# thermocouple_2.net
KiCad netlist of a schematic drawn in Altium Designer
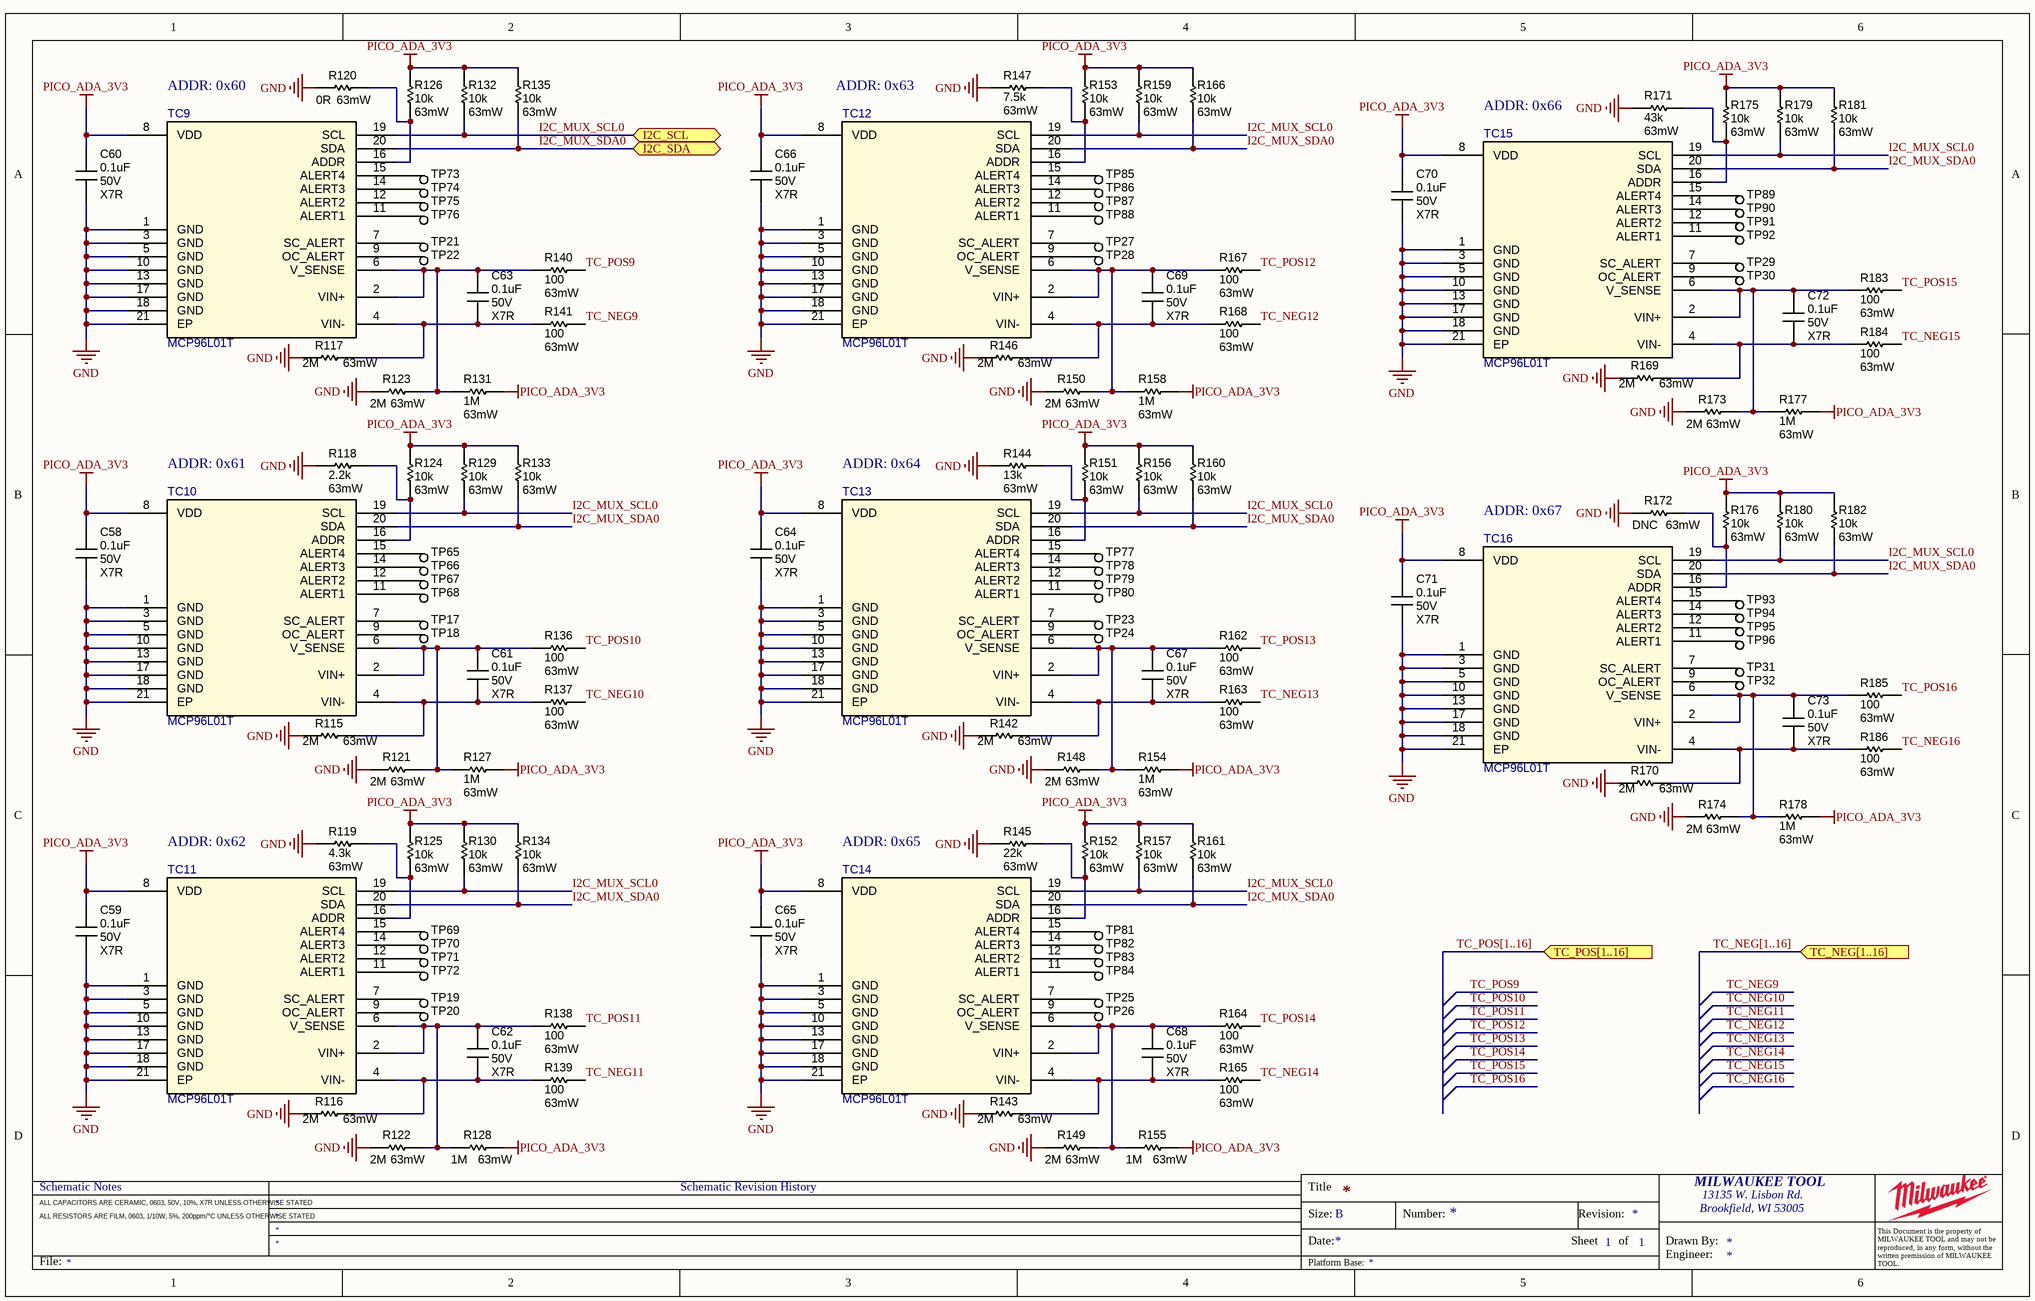
[diagram p0: thermocouple_2.SchDoc]

(export (version "E")
  (design (tool "Eeschema 10.0.6"))
  (components
    (comp (ref "C58")
      (value "0.1uF")
      (footprint "CAPC1608X09N")
      (description "CAP CER 0.1UF 50V X7R 0603")
      (fields
        (field (name "TOLERANCE") "10%")
        (field (name "MFR") "KEMET")
        (field (name "VOLTAGE RATING") "50V")
        (field (name "TEMP COEFF") "X7R")
      )
      (libsource (lib "General_Library") (part "CMP-004-0070"))
    )
    (comp (ref "C59")
      (value "0.1uF")
      (footprint "CAPC1608X09N")
      (description "CAP CER 0.1UF 50V X7R 0603")
      (fields
        (field (name "TOLERANCE") "10%")
        (field (name "MFR") "KEMET")
        (field (name "VOLTAGE RATING") "50V")
        (field (name "TEMP COEFF") "X7R")
      )
      (libsource (lib "General_Library") (part "CMP-004-0070"))
    )
    (comp (ref "C60")
      (value "0.1uF")
      (footprint "CAPC1608X09N")
      (description "CAP CER 0.1UF 50V X7R 0603")
      (fields
        (field (name "TOLERANCE") "10%")
        (field (name "MFR") "KEMET")
        (field (name "VOLTAGE RATING") "50V")
        (field (name "TEMP COEFF") "X7R")
      )
      (libsource (lib "General_Library") (part "CMP-004-0070"))
    )
    (comp (ref "C61")
      (value "0.1uF")
      (footprint "CAPC1005X06N")
      (description "CAP CER SMD 0.1UF 50V X7R 0402")
      (fields
        (field (name "TOLERANCE") "10%")
        (field (name "MFR") "Murata Electronics")
        (field (name "VOLTAGE RATING") "50V")
        (field (name "TEMP COEFF") "X7R")
      )
      (libsource (lib "General_Library") (part "CMP-004-0076"))
    )
    (comp (ref "C62")
      (value "0.1uF")
      (footprint "CAPC1005X06N")
      (description "CAP CER SMD 0.1UF 50V X7R 0402")
      (fields
        (field (name "TOLERANCE") "10%")
        (field (name "MFR") "Murata Electronics")
        (field (name "VOLTAGE RATING") "50V")
        (field (name "TEMP COEFF") "X7R")
      )
      (libsource (lib "General_Library") (part "CMP-004-0076"))
    )
    (comp (ref "C63")
      (value "0.1uF")
      (footprint "CAPC1005X06N")
      (description "CAP CER SMD 0.1UF 50V X7R 0402")
      (fields
        (field (name "TOLERANCE") "10%")
        (field (name "MFR") "Murata Electronics")
        (field (name "VOLTAGE RATING") "50V")
        (field (name "TEMP COEFF") "X7R")
      )
      (libsource (lib "General_Library") (part "CMP-004-0076"))
    )
    (comp (ref "C64")
      (value "0.1uF")
      (footprint "CAPC1608X09N")
      (description "CAP CER 0.1UF 50V X7R 0603")
      (fields
        (field (name "TOLERANCE") "10%")
        (field (name "MFR") "KEMET")
        (field (name "VOLTAGE RATING") "50V")
        (field (name "TEMP COEFF") "X7R")
      )
      (libsource (lib "General_Library") (part "CMP-004-0070"))
    )
    (comp (ref "C65")
      (value "0.1uF")
      (footprint "CAPC1608X09N")
      (description "CAP CER 0.1UF 50V X7R 0603")
      (fields
        (field (name "TOLERANCE") "10%")
        (field (name "MFR") "KEMET")
        (field (name "VOLTAGE RATING") "50V")
        (field (name "TEMP COEFF") "X7R")
      )
      (libsource (lib "General_Library") (part "CMP-004-0070"))
    )
    (comp (ref "C66")
      (value "0.1uF")
      (footprint "CAPC1608X09N")
      (description "CAP CER 0.1UF 50V X7R 0603")
      (fields
        (field (name "TOLERANCE") "10%")
        (field (name "MFR") "KEMET")
        (field (name "VOLTAGE RATING") "50V")
        (field (name "TEMP COEFF") "X7R")
      )
      (libsource (lib "General_Library") (part "CMP-004-0070"))
    )
    (comp (ref "C67")
      (value "0.1uF")
      (footprint "CAPC1005X06N")
      (description "CAP CER SMD 0.1UF 50V X7R 0402")
      (fields
        (field (name "TOLERANCE") "10%")
        (field (name "MFR") "Murata Electronics")
        (field (name "VOLTAGE RATING") "50V")
        (field (name "TEMP COEFF") "X7R")
      )
      (libsource (lib "General_Library") (part "CMP-004-0076"))
    )
    (comp (ref "C68")
      (value "0.1uF")
      (footprint "CAPC1005X06N")
      (description "CAP CER SMD 0.1UF 50V X7R 0402")
      (fields
        (field (name "TOLERANCE") "10%")
        (field (name "MFR") "Murata Electronics")
        (field (name "VOLTAGE RATING") "50V")
        (field (name "TEMP COEFF") "X7R")
      )
      (libsource (lib "General_Library") (part "CMP-004-0076"))
    )
    (comp (ref "C69")
      (value "0.1uF")
      (footprint "CAPC1005X06N")
      (description "CAP CER SMD 0.1UF 50V X7R 0402")
      (fields
        (field (name "TOLERANCE") "10%")
        (field (name "MFR") "Murata Electronics")
        (field (name "VOLTAGE RATING") "50V")
        (field (name "TEMP COEFF") "X7R")
      )
      (libsource (lib "General_Library") (part "CMP-004-0076"))
    )
    (comp (ref "C70")
      (value "0.1uF")
      (footprint "CAPC1608X09N")
      (description "CAP CER 0.1UF 50V X7R 0603")
      (fields
        (field (name "TOLERANCE") "10%")
        (field (name "MFR") "KEMET")
        (field (name "VOLTAGE RATING") "50V")
        (field (name "TEMP COEFF") "X7R")
      )
      (libsource (lib "General_Library") (part "CMP-004-0070"))
    )
    (comp (ref "C71")
      (value "0.1uF")
      (footprint "CAPC1608X09N")
      (description "CAP CER 0.1UF 50V X7R 0603")
      (fields
        (field (name "TOLERANCE") "10%")
        (field (name "MFR") "KEMET")
        (field (name "VOLTAGE RATING") "50V")
        (field (name "TEMP COEFF") "X7R")
      )
      (libsource (lib "General_Library") (part "CMP-004-0070"))
    )
    (comp (ref "C72")
      (value "0.1uF")
      (footprint "CAPC1005X06N")
      (description "CAP CER SMD 0.1UF 50V X7R 0402")
      (fields
        (field (name "TOLERANCE") "10%")
        (field (name "MFR") "Murata Electronics")
        (field (name "VOLTAGE RATING") "50V")
        (field (name "TEMP COEFF") "X7R")
      )
      (libsource (lib "General_Library") (part "CMP-004-0076"))
    )
    (comp (ref "C73")
      (value "0.1uF")
      (footprint "CAPC1005X06N")
      (description "CAP CER SMD 0.1UF 50V X7R 0402")
      (fields
        (field (name "TOLERANCE") "10%")
        (field (name "MFR") "Murata Electronics")
        (field (name "VOLTAGE RATING") "50V")
        (field (name "TEMP COEFF") "X7R")
      )
      (libsource (lib "General_Library") (part "CMP-004-0076"))
    )
    (comp (ref "R115")
      (value "2M")
      (footprint "RESC1005X04N")
      (description "RES SMD 2M OHM 1% 1/16W 0402")
      (fields (field (name "TOLERANCE") "1%") (field (name "MFR") "YAGEO") (field (name "WATTAGE") "63mW"))
      (libsource (lib "General_Library") (part "CMP-025-0172"))
    )
    (comp (ref "R116")
      (value "2M")
      (footprint "RESC1005X04N")
      (description "RES SMD 2M OHM 1% 1/16W 0402")
      (fields (field (name "TOLERANCE") "1%") (field (name "MFR") "YAGEO") (field (name "WATTAGE") "63mW"))
      (libsource (lib "General_Library") (part "CMP-025-0172"))
    )
    (comp (ref "R117")
      (value "2M")
      (footprint "RESC1005X04N")
      (description "RES SMD 2M OHM 1% 1/16W 0402")
      (fields (field (name "TOLERANCE") "1%") (field (name "MFR") "YAGEO") (field (name "WATTAGE") "63mW"))
      (libsource (lib "General_Library") (part "CMP-025-0172"))
    )
    (comp (ref "R118")
      (value "2.2k")
      (footprint "RESC1005X04N")
      (description "RES SMD 2.2K OHM 1% 1/16W 0402")
      (fields (field (name "TOLERANCE") "1%") (field (name "MFR") "YAGEO") (field (name "WATTAGE") "63mW"))
      (libsource (lib "General_Library") (part "CMP-025-0171"))
    )
    (comp (ref "R119")
      (value "4.3k")
      (footprint "RESC1005X04N")
      (description "RES SMD 4.3K OHM 1% 1/16W 0402")
      (fields (field (name "TOLERANCE") "1%") (field (name "MFR") "Yageo") (field (name "WATTAGE") "63mW"))
      (libsource (lib "General_Library") (part "CMP-025-0176"))
    )
    (comp (ref "R120")
      (value "0R")
      (footprint "RESC1005X04N")
      (description "RES SMD 0 OHM JUMPER 1/16W 0402")
      (fields
        (field (name "MFR") "Stackpole Electronics Inc")
        (field (name "TOLERANCE") "Jumper")
        (field (name "WATTAGE") "63mW")
      )
      (libsource (lib "General_Library") (part "CMP-025-0102"))
    )
    (comp (ref "R121")
      (value "2M")
      (footprint "RESC1005X04N")
      (description "RES SMD 2M OHM 1% 1/16W 0402")
      (fields (field (name "TOLERANCE") "1%") (field (name "MFR") "YAGEO") (field (name "WATTAGE") "63mW"))
      (libsource (lib "General_Library") (part "CMP-025-0172"))
    )
    (comp (ref "R122")
      (value "2M")
      (footprint "RESC1005X04N")
      (description "RES SMD 2M OHM 1% 1/16W 0402")
      (fields (field (name "TOLERANCE") "1%") (field (name "MFR") "YAGEO") (field (name "WATTAGE") "63mW"))
      (libsource (lib "General_Library") (part "CMP-025-0172"))
    )
    (comp (ref "R123")
      (value "2M")
      (footprint "RESC1005X04N")
      (description "RES SMD 2M OHM 1% 1/16W 0402")
      (fields (field (name "TOLERANCE") "1%") (field (name "MFR") "YAGEO") (field (name "WATTAGE") "63mW"))
      (libsource (lib "General_Library") (part "CMP-025-0172"))
    )
    (comp (ref "R124")
      (value "10k")
      (footprint "RESC1005X04N")
      (description "RES SMD 10K OHM 0.5% 1/16W 0402")
      (fields
        (field (name "MFR") "Panasonic Electronic Components")
        (field (name "TOLERANCE") "0.5%")
        (field (name "WATTAGE") "63mW")
      )
      (libsource (lib "Schlib1") (part "CMP-025-0026"))
    )
    (comp (ref "R125")
      (value "10k")
      (footprint "RESC1005X04N")
      (description "RES SMD 10K OHM 0.5% 1/16W 0402")
      (fields
        (field (name "MFR") "Panasonic Electronic Components")
        (field (name "TOLERANCE") "0.5%")
        (field (name "WATTAGE") "63mW")
      )
      (libsource (lib "Schlib1") (part "CMP-025-0026"))
    )
    (comp (ref "R126")
      (value "10k")
      (footprint "RESC1005X04N")
      (description "RES SMD 10K OHM 0.5% 1/16W 0402")
      (fields
        (field (name "MFR") "Panasonic Electronic Components")
        (field (name "TOLERANCE") "0.5%")
        (field (name "WATTAGE") "63mW")
      )
      (libsource (lib "Schlib1") (part "CMP-025-0026"))
    )
    (comp (ref "R127")
      (value "1M")
      (footprint "RESC1005X04N")
      (description "RES SMD 1M OHM 1% 1/16W 0402")
      (fields (field (name "TOLERANCE") "1%") (field (name "MFR") "YAGEO") (field (name "WATTAGE") "63mW"))
      (libsource (lib "General_Library") (part "CMP-025-0173"))
    )
    (comp (ref "R128")
      (value "1M")
      (footprint "RESC1005X04N")
      (description "RES SMD 1M OHM 1% 1/16W 0402")
      (fields (field (name "TOLERANCE") "1%") (field (name "MFR") "YAGEO") (field (name "WATTAGE") "63mW"))
      (libsource (lib "General_Library") (part "CMP-025-0173"))
    )
    (comp (ref "R129")
      (value "10k")
      (footprint "RESC1005X04N")
      (description "RES SMD 10K OHM 0.5% 1/16W 0402")
      (fields
        (field (name "MFR") "Panasonic Electronic Components")
        (field (name "TOLERANCE") "0.5%")
        (field (name "WATTAGE") "63mW")
      )
      (libsource (lib "Schlib1") (part "CMP-025-0026"))
    )
    (comp (ref "R130")
      (value "10k")
      (footprint "RESC1005X04N")
      (description "RES SMD 10K OHM 0.5% 1/16W 0402")
      (fields
        (field (name "MFR") "Panasonic Electronic Components")
        (field (name "TOLERANCE") "0.5%")
        (field (name "WATTAGE") "63mW")
      )
      (libsource (lib "Schlib1") (part "CMP-025-0026"))
    )
    (comp (ref "R131")
      (value "1M")
      (footprint "RESC1005X04N")
      (description "RES SMD 1M OHM 1% 1/16W 0402")
      (fields (field (name "TOLERANCE") "1%") (field (name "MFR") "YAGEO") (field (name "WATTAGE") "63mW"))
      (libsource (lib "General_Library") (part "CMP-025-0173"))
    )
    (comp (ref "R132")
      (value "10k")
      (footprint "RESC1005X04N")
      (description "RES SMD 10K OHM 0.5% 1/16W 0402")
      (fields
        (field (name "MFR") "Panasonic Electronic Components")
        (field (name "TOLERANCE") "0.5%")
        (field (name "WATTAGE") "63mW")
      )
      (libsource (lib "Schlib1") (part "CMP-025-0026"))
    )
    (comp (ref "R133")
      (value "10k")
      (footprint "RESC1005X04N")
      (description "RES SMD 10K OHM 0.5% 1/16W 0402")
      (fields
        (field (name "MFR") "Panasonic Electronic Components")
        (field (name "TOLERANCE") "0.5%")
        (field (name "WATTAGE") "63mW")
      )
      (libsource (lib "Schlib1") (part "CMP-025-0026"))
    )
    (comp (ref "R134")
      (value "10k")
      (footprint "RESC1005X04N")
      (description "RES SMD 10K OHM 0.5% 1/16W 0402")
      (fields
        (field (name "MFR") "Panasonic Electronic Components")
        (field (name "TOLERANCE") "0.5%")
        (field (name "WATTAGE") "63mW")
      )
      (libsource (lib "Schlib1") (part "CMP-025-0026"))
    )
    (comp (ref "R135")
      (value "10k")
      (footprint "RESC1005X04N")
      (description "RES SMD 10K OHM 0.5% 1/16W 0402")
      (fields
        (field (name "MFR") "Panasonic Electronic Components")
        (field (name "TOLERANCE") "0.5%")
        (field (name "WATTAGE") "63mW")
      )
      (libsource (lib "Schlib1") (part "CMP-025-0026"))
    )
    (comp (ref "R136")
      (value "100")
      (footprint "RESC1005X04N")
      (description "RES SMD 100 OHM 1% 1/16W 0402")
      (fields
        (field (name "TOLERANCE") "1%")
        (field (name "MFR") "Stackpole Electronics Inc")
        (field (name "WATTAGE") "63mW")
      )
      (libsource (lib "General_Library") (part "CMP-025-0156"))
    )
    (comp (ref "R137")
      (value "100")
      (footprint "RESC1005X04N")
      (description "RES SMD 100 OHM 1% 1/16W 0402")
      (fields
        (field (name "TOLERANCE") "1%")
        (field (name "MFR") "Stackpole Electronics Inc")
        (field (name "WATTAGE") "63mW")
      )
      (libsource (lib "General_Library") (part "CMP-025-0156"))
    )
    (comp (ref "R138")
      (value "100")
      (footprint "RESC1005X04N")
      (description "RES SMD 100 OHM 1% 1/16W 0402")
      (fields
        (field (name "TOLERANCE") "1%")
        (field (name "MFR") "Stackpole Electronics Inc")
        (field (name "WATTAGE") "63mW")
      )
      (libsource (lib "General_Library") (part "CMP-025-0156"))
    )
    (comp (ref "R139")
      (value "100")
      (footprint "RESC1005X04N")
      (description "RES SMD 100 OHM 1% 1/16W 0402")
      (fields
        (field (name "TOLERANCE") "1%")
        (field (name "MFR") "Stackpole Electronics Inc")
        (field (name "WATTAGE") "63mW")
      )
      (libsource (lib "General_Library") (part "CMP-025-0156"))
    )
    (comp (ref "R140")
      (value "100")
      (footprint "RESC1005X04N")
      (description "RES SMD 100 OHM 1% 1/16W 0402")
      (fields
        (field (name "TOLERANCE") "1%")
        (field (name "MFR") "Stackpole Electronics Inc")
        (field (name "WATTAGE") "63mW")
      )
      (libsource (lib "General_Library") (part "CMP-025-0156"))
    )
    (comp (ref "R141")
      (value "100")
      (footprint "RESC1005X04N")
      (description "RES SMD 100 OHM 1% 1/16W 0402")
      (fields
        (field (name "TOLERANCE") "1%")
        (field (name "MFR") "Stackpole Electronics Inc")
        (field (name "WATTAGE") "63mW")
      )
      (libsource (lib "General_Library") (part "CMP-025-0156"))
    )
    (comp (ref "R142")
      (value "2M")
      (footprint "RESC1005X04N")
      (description "RES SMD 2M OHM 1% 1/16W 0402")
      (fields (field (name "TOLERANCE") "1%") (field (name "MFR") "YAGEO") (field (name "WATTAGE") "63mW"))
      (libsource (lib "General_Library") (part "CMP-025-0172"))
    )
    (comp (ref "R143")
      (value "2M")
      (footprint "RESC1005X04N")
      (description "RES SMD 2M OHM 1% 1/16W 0402")
      (fields (field (name "TOLERANCE") "1%") (field (name "MFR") "YAGEO") (field (name "WATTAGE") "63mW"))
      (libsource (lib "General_Library") (part "CMP-025-0172"))
    )
    (comp (ref "R144")
      (value "13k")
      (footprint "RESC1005X04N")
      (description "RES SMD 13K OHM 1% 1/16W 0402")
      (fields (field (name "TOLERANCE") "1%") (field (name "MFR") "Yageo") (field (name "WATTAGE") "63mW"))
      (libsource (lib "General_Library") (part "CMP-025-0178"))
    )
    (comp (ref "R145")
      (value "22k")
      (footprint "RESC1005X04N")
      (description "RES SMD 22K OHM 1% 1/16W 0402")
      (fields (field (name "TOLERANCE") "1%") (field (name "MFR") "Yageo") (field (name "WATTAGE") "63mW"))
      (libsource (lib "General_Library") (part "CMP-025-0179"))
    )
    (comp (ref "R146")
      (value "2M")
      (footprint "RESC1005X04N")
      (description "RES SMD 2M OHM 1% 1/16W 0402")
      (fields (field (name "TOLERANCE") "1%") (field (name "MFR") "YAGEO") (field (name "WATTAGE") "63mW"))
      (libsource (lib "General_Library") (part "CMP-025-0172"))
    )
    (comp (ref "R147")
      (value "7.5k")
      (footprint "RESC1005X04N")
      (description "RES SMD 7.5K OHM 1% 1/16W 0402")
      (fields (field (name "TOLERANCE") "1%") (field (name "MFR") "Yageo") (field (name "WATTAGE") "63mW"))
      (libsource (lib "General_Library") (part "CMP-025-0177"))
    )
    (comp (ref "R148")
      (value "2M")
      (footprint "RESC1005X04N")
      (description "RES SMD 2M OHM 1% 1/16W 0402")
      (fields (field (name "TOLERANCE") "1%") (field (name "MFR") "YAGEO") (field (name "WATTAGE") "63mW"))
      (libsource (lib "General_Library") (part "CMP-025-0172"))
    )
    (comp (ref "R149")
      (value "2M")
      (footprint "RESC1005X04N")
      (description "RES SMD 2M OHM 1% 1/16W 0402")
      (fields (field (name "TOLERANCE") "1%") (field (name "MFR") "YAGEO") (field (name "WATTAGE") "63mW"))
      (libsource (lib "General_Library") (part "CMP-025-0172"))
    )
    (comp (ref "R150")
      (value "2M")
      (footprint "RESC1005X04N")
      (description "RES SMD 2M OHM 1% 1/16W 0402")
      (fields (field (name "TOLERANCE") "1%") (field (name "MFR") "YAGEO") (field (name "WATTAGE") "63mW"))
      (libsource (lib "General_Library") (part "CMP-025-0172"))
    )
    (comp (ref "R151")
      (value "10k")
      (footprint "RESC1005X04N")
      (description "RES SMD 10K OHM 0.5% 1/16W 0402")
      (fields
        (field (name "MFR") "Panasonic Electronic Components")
        (field (name "TOLERANCE") "0.5%")
        (field (name "WATTAGE") "63mW")
      )
      (libsource (lib "Schlib1") (part "CMP-025-0026"))
    )
    (comp (ref "R152")
      (value "10k")
      (footprint "RESC1005X04N")
      (description "RES SMD 10K OHM 0.5% 1/16W 0402")
      (fields
        (field (name "MFR") "Panasonic Electronic Components")
        (field (name "TOLERANCE") "0.5%")
        (field (name "WATTAGE") "63mW")
      )
      (libsource (lib "Schlib1") (part "CMP-025-0026"))
    )
    (comp (ref "R153")
      (value "10k")
      (footprint "RESC1005X04N")
      (description "RES SMD 10K OHM 0.5% 1/16W 0402")
      (fields
        (field (name "MFR") "Panasonic Electronic Components")
        (field (name "TOLERANCE") "0.5%")
        (field (name "WATTAGE") "63mW")
      )
      (libsource (lib "Schlib1") (part "CMP-025-0026"))
    )
    (comp (ref "R154")
      (value "1M")
      (footprint "RESC1005X04N")
      (description "RES SMD 1M OHM 1% 1/16W 0402")
      (fields (field (name "TOLERANCE") "1%") (field (name "MFR") "YAGEO") (field (name "WATTAGE") "63mW"))
      (libsource (lib "General_Library") (part "CMP-025-0173"))
    )
    (comp (ref "R155")
      (value "1M")
      (footprint "RESC1005X04N")
      (description "RES SMD 1M OHM 1% 1/16W 0402")
      (fields (field (name "TOLERANCE") "1%") (field (name "MFR") "YAGEO") (field (name "WATTAGE") "63mW"))
      (libsource (lib "General_Library") (part "CMP-025-0173"))
    )
    (comp (ref "R156")
      (value "10k")
      (footprint "RESC1005X04N")
      (description "RES SMD 10K OHM 0.5% 1/16W 0402")
      (fields
        (field (name "MFR") "Panasonic Electronic Components")
        (field (name "TOLERANCE") "0.5%")
        (field (name "WATTAGE") "63mW")
      )
      (libsource (lib "Schlib1") (part "CMP-025-0026"))
    )
    (comp (ref "R157")
      (value "10k")
      (footprint "RESC1005X04N")
      (description "RES SMD 10K OHM 0.5% 1/16W 0402")
      (fields
        (field (name "MFR") "Panasonic Electronic Components")
        (field (name "TOLERANCE") "0.5%")
        (field (name "WATTAGE") "63mW")
      )
      (libsource (lib "Schlib1") (part "CMP-025-0026"))
    )
    (comp (ref "R158")
      (value "1M")
      (footprint "RESC1005X04N")
      (description "RES SMD 1M OHM 1% 1/16W 0402")
      (fields (field (name "TOLERANCE") "1%") (field (name "MFR") "YAGEO") (field (name "WATTAGE") "63mW"))
      (libsource (lib "General_Library") (part "CMP-025-0173"))
    )
    (comp (ref "R159")
      (value "10k")
      (footprint "RESC1005X04N")
      (description "RES SMD 10K OHM 0.5% 1/16W 0402")
      (fields
        (field (name "MFR") "Panasonic Electronic Components")
        (field (name "TOLERANCE") "0.5%")
        (field (name "WATTAGE") "63mW")
      )
      (libsource (lib "Schlib1") (part "CMP-025-0026"))
    )
    (comp (ref "R160")
      (value "10k")
      (footprint "RESC1005X04N")
      (description "RES SMD 10K OHM 0.5% 1/16W 0402")
      (fields
        (field (name "MFR") "Panasonic Electronic Components")
        (field (name "TOLERANCE") "0.5%")
        (field (name "WATTAGE") "63mW")
      )
      (libsource (lib "Schlib1") (part "CMP-025-0026"))
    )
    (comp (ref "R161")
      (value "10k")
      (footprint "RESC1005X04N")
      (description "RES SMD 10K OHM 0.5% 1/16W 0402")
      (fields
        (field (name "MFR") "Panasonic Electronic Components")
        (field (name "TOLERANCE") "0.5%")
        (field (name "WATTAGE") "63mW")
      )
      (libsource (lib "Schlib1") (part "CMP-025-0026"))
    )
    (comp (ref "R162")
      (value "100")
      (footprint "RESC1005X04N")
      (description "RES SMD 100 OHM 1% 1/16W 0402")
      (fields
        (field (name "TOLERANCE") "1%")
        (field (name "MFR") "Stackpole Electronics Inc")
        (field (name "WATTAGE") "63mW")
      )
      (libsource (lib "General_Library") (part "CMP-025-0156"))
    )
    (comp (ref "R163")
      (value "100")
      (footprint "RESC1005X04N")
      (description "RES SMD 100 OHM 1% 1/16W 0402")
      (fields
        (field (name "TOLERANCE") "1%")
        (field (name "MFR") "Stackpole Electronics Inc")
        (field (name "WATTAGE") "63mW")
      )
      (libsource (lib "General_Library") (part "CMP-025-0156"))
    )
    (comp (ref "R164")
      (value "100")
      (footprint "RESC1005X04N")
      (description "RES SMD 100 OHM 1% 1/16W 0402")
      (fields
        (field (name "TOLERANCE") "1%")
        (field (name "MFR") "Stackpole Electronics Inc")
        (field (name "WATTAGE") "63mW")
      )
      (libsource (lib "General_Library") (part "CMP-025-0156"))
    )
    (comp (ref "R165")
      (value "100")
      (footprint "RESC1005X04N")
      (description "RES SMD 100 OHM 1% 1/16W 0402")
      (fields
        (field (name "TOLERANCE") "1%")
        (field (name "MFR") "Stackpole Electronics Inc")
        (field (name "WATTAGE") "63mW")
      )
      (libsource (lib "General_Library") (part "CMP-025-0156"))
    )
    (comp (ref "R166")
      (value "10k")
      (footprint "RESC1005X04N")
      (description "RES SMD 10K OHM 0.5% 1/16W 0402")
      (fields
        (field (name "MFR") "Panasonic Electronic Components")
        (field (name "TOLERANCE") "0.5%")
        (field (name "WATTAGE") "63mW")
      )
      (libsource (lib "Schlib1") (part "CMP-025-0026"))
    )
    (comp (ref "R167")
      (value "100")
      (footprint "RESC1005X04N")
      (description "RES SMD 100 OHM 1% 1/16W 0402")
      (fields
        (field (name "TOLERANCE") "1%")
        (field (name "MFR") "Stackpole Electronics Inc")
        (field (name "WATTAGE") "63mW")
      )
      (libsource (lib "General_Library") (part "CMP-025-0156"))
    )
    (comp (ref "R168")
      (value "100")
      (footprint "RESC1005X04N")
      (description "RES SMD 100 OHM 1% 1/16W 0402")
      (fields
        (field (name "TOLERANCE") "1%")
        (field (name "MFR") "Stackpole Electronics Inc")
        (field (name "WATTAGE") "63mW")
      )
      (libsource (lib "General_Library") (part "CMP-025-0156"))
    )
    (comp (ref "R169")
      (value "2M")
      (footprint "RESC1005X04N")
      (description "RES SMD 2M OHM 1% 1/16W 0402")
      (fields (field (name "TOLERANCE") "1%") (field (name "MFR") "YAGEO") (field (name "WATTAGE") "63mW"))
      (libsource (lib "General_Library") (part "CMP-025-0172"))
    )
    (comp (ref "R170")
      (value "2M")
      (footprint "RESC1005X04N")
      (description "RES SMD 2M OHM 1% 1/16W 0402")
      (fields (field (name "TOLERANCE") "1%") (field (name "MFR") "YAGEO") (field (name "WATTAGE") "63mW"))
      (libsource (lib "General_Library") (part "CMP-025-0172"))
    )
    (comp (ref "R171")
      (value "43k")
      (footprint "RESC1005X04N")
      (description "RES SMD 43K OHM 1% 1/16W 0402")
      (fields (field (name "TOLERANCE") "1%") (field (name "MFR") "Yageo") (field (name "WATTAGE") "63mW"))
      (libsource (lib "General_Library") (part "CMP-025-0180"))
    )
    (comp (ref "R172")
      (value "DNC")
      (footprint "RESC1005X04N")
      (description "RES SMD 0 OHM JUMPER 1/16W 0402")
      (fields
        (field (name "MFR") "Stackpole Electronics Inc")
        (field (name "TOLERANCE") "Jumper")
        (field (name "WATTAGE") "63mW")
      )
      (libsource (lib "General_Library") (part "CMP-025-0102"))
    )
    (comp (ref "R173")
      (value "2M")
      (footprint "RESC1005X04N")
      (description "RES SMD 2M OHM 1% 1/16W 0402")
      (fields (field (name "TOLERANCE") "1%") (field (name "MFR") "YAGEO") (field (name "WATTAGE") "63mW"))
      (libsource (lib "General_Library") (part "CMP-025-0172"))
    )
    (comp (ref "R174")
      (value "2M")
      (footprint "RESC1005X04N")
      (description "RES SMD 2M OHM 1% 1/16W 0402")
      (fields (field (name "TOLERANCE") "1%") (field (name "MFR") "YAGEO") (field (name "WATTAGE") "63mW"))
      (libsource (lib "General_Library") (part "CMP-025-0172"))
    )
    (comp (ref "R175")
      (value "10k")
      (footprint "RESC1005X04N")
      (description "RES SMD 10K OHM 0.5% 1/16W 0402")
      (fields
        (field (name "MFR") "Panasonic Electronic Components")
        (field (name "TOLERANCE") "0.5%")
        (field (name "WATTAGE") "63mW")
      )
      (libsource (lib "Schlib1") (part "CMP-025-0026"))
    )
    (comp (ref "R176")
      (value "10k")
      (footprint "RESC1005X04N")
      (description "RES SMD 10K OHM 0.5% 1/16W 0402")
      (fields
        (field (name "MFR") "Panasonic Electronic Components")
        (field (name "TOLERANCE") "0.5%")
        (field (name "WATTAGE") "63mW")
      )
      (libsource (lib "Schlib1") (part "CMP-025-0026"))
    )
    (comp (ref "R177")
      (value "1M")
      (footprint "RESC1005X04N")
      (description "RES SMD 1M OHM 1% 1/16W 0402")
      (fields (field (name "TOLERANCE") "1%") (field (name "MFR") "YAGEO") (field (name "WATTAGE") "63mW"))
      (libsource (lib "General_Library") (part "CMP-025-0173"))
    )
    (comp (ref "R178")
      (value "1M")
      (footprint "RESC1005X04N")
      (description "RES SMD 1M OHM 1% 1/16W 0402")
      (fields (field (name "TOLERANCE") "1%") (field (name "MFR") "YAGEO") (field (name "WATTAGE") "63mW"))
      (libsource (lib "General_Library") (part "CMP-025-0173"))
    )
    (comp (ref "R179")
      (value "10k")
      (footprint "RESC1005X04N")
      (description "RES SMD 10K OHM 0.5% 1/16W 0402")
      (fields
        (field (name "MFR") "Panasonic Electronic Components")
        (field (name "TOLERANCE") "0.5%")
        (field (name "WATTAGE") "63mW")
      )
      (libsource (lib "Schlib1") (part "CMP-025-0026"))
    )
    (comp (ref "R180")
      (value "10k")
      (footprint "RESC1005X04N")
      (description "RES SMD 10K OHM 0.5% 1/16W 0402")
      (fields
        (field (name "MFR") "Panasonic Electronic Components")
        (field (name "TOLERANCE") "0.5%")
        (field (name "WATTAGE") "63mW")
      )
      (libsource (lib "Schlib1") (part "CMP-025-0026"))
    )
    (comp (ref "R181")
      (value "10k")
      (footprint "RESC1005X04N")
      (description "RES SMD 10K OHM 0.5% 1/16W 0402")
      (fields
        (field (name "MFR") "Panasonic Electronic Components")
        (field (name "TOLERANCE") "0.5%")
        (field (name "WATTAGE") "63mW")
      )
      (libsource (lib "Schlib1") (part "CMP-025-0026"))
    )
    (comp (ref "R182")
      (value "10k")
      (footprint "RESC1005X04N")
      (description "RES SMD 10K OHM 0.5% 1/16W 0402")
      (fields
        (field (name "MFR") "Panasonic Electronic Components")
        (field (name "TOLERANCE") "0.5%")
        (field (name "WATTAGE") "63mW")
      )
      (libsource (lib "Schlib1") (part "CMP-025-0026"))
    )
    (comp (ref "R183")
      (value "100")
      (footprint "RESC1005X04N")
      (description "RES SMD 100 OHM 1% 1/16W 0402")
      (fields
        (field (name "TOLERANCE") "1%")
        (field (name "MFR") "Stackpole Electronics Inc")
        (field (name "WATTAGE") "63mW")
      )
      (libsource (lib "General_Library") (part "CMP-025-0156"))
    )
    (comp (ref "R184")
      (value "100")
      (footprint "RESC1005X04N")
      (description "RES SMD 100 OHM 1% 1/16W 0402")
      (fields
        (field (name "TOLERANCE") "1%")
        (field (name "MFR") "Stackpole Electronics Inc")
        (field (name "WATTAGE") "63mW")
      )
      (libsource (lib "General_Library") (part "CMP-025-0156"))
    )
    (comp (ref "R185")
      (value "100")
      (footprint "RESC1005X04N")
      (description "RES SMD 100 OHM 1% 1/16W 0402")
      (fields
        (field (name "TOLERANCE") "1%")
        (field (name "MFR") "Stackpole Electronics Inc")
        (field (name "WATTAGE") "63mW")
      )
      (libsource (lib "General_Library") (part "CMP-025-0156"))
    )
    (comp (ref "R186")
      (value "100")
      (footprint "RESC1005X04N")
      (description "RES SMD 100 OHM 1% 1/16W 0402")
      (fields
        (field (name "TOLERANCE") "1%")
        (field (name "MFR") "Stackpole Electronics Inc")
        (field (name "WATTAGE") "63mW")
      )
      (libsource (lib "General_Library") (part "CMP-025-0156"))
    )
    (comp (ref "TC9")
      (value "MCP96L01T")
      (footprint "Footprints:QFN65P500X500X100_HS-21N")
      (description "IC THERMOCOUPLE AMPLIFIER I2C")
      (fields (field (name "MFR") "Microchip"))
      (libsource (lib "Symbols") (part "CMP-017-0115"))
    )
    (comp (ref "TC10")
      (value "MCP96L01T")
      (footprint "Footprints:QFN65P500X500X100_HS-21N")
      (description "IC THERMOCOUPLE AMPLIFIER I2C")
      (fields (field (name "MFR") "Microchip"))
      (libsource (lib "Symbols") (part "CMP-017-0115"))
    )
    (comp (ref "TC11")
      (value "MCP96L01T")
      (footprint "Footprints:QFN65P500X500X100_HS-21N")
      (description "IC THERMOCOUPLE AMPLIFIER I2C")
      (fields (field (name "MFR") "Microchip"))
      (libsource (lib "Symbols") (part "CMP-017-0115"))
    )
    (comp (ref "TC12")
      (value "MCP96L01T")
      (footprint "Footprints:QFN65P500X500X100_HS-21N")
      (description "IC THERMOCOUPLE AMPLIFIER I2C")
      (fields (field (name "MFR") "Microchip"))
      (libsource (lib "Symbols") (part "CMP-017-0115"))
    )
    (comp (ref "TC13")
      (value "MCP96L01T")
      (footprint "Footprints:QFN65P500X500X100_HS-21N")
      (description "IC THERMOCOUPLE AMPLIFIER I2C")
      (fields (field (name "MFR") "Microchip"))
      (libsource (lib "Symbols") (part "CMP-017-0115"))
    )
    (comp (ref "TC14")
      (value "MCP96L01T")
      (footprint "Footprints:QFN65P500X500X100_HS-21N")
      (description "IC THERMOCOUPLE AMPLIFIER I2C")
      (fields (field (name "MFR") "Microchip"))
      (libsource (lib "Symbols") (part "CMP-017-0115"))
    )
    (comp (ref "TC15")
      (value "MCP96L01T")
      (footprint "Footprints:QFN65P500X500X100_HS-21N")
      (description "IC THERMOCOUPLE AMPLIFIER I2C")
      (fields (field (name "MFR") "Microchip"))
      (libsource (lib "Symbols") (part "CMP-017-0115"))
    )
    (comp (ref "TC16")
      (value "MCP96L01T")
      (footprint "Footprints:QFN65P500X500X100_HS-21N")
      (description "IC THERMOCOUPLE AMPLIFIER I2C")
      (fields (field (name "MFR") "Microchip"))
      (libsource (lib "Symbols") (part "CMP-017-0115"))
    )
    (comp (ref "TP17")
      (value "TP_SMT_1MM_CIR")
      (footprint "TP_SMT_1.0MM_CIR")
      (description "TP SMT 1mm Circle")
      (libsource (lib "General_Library") (part "CMP-019-0006"))
    )
    (comp (ref "TP18")
      (value "TP_SMT_1MM_CIR")
      (footprint "TP_SMT_1.0MM_CIR")
      (description "TP SMT 1mm Circle")
      (libsource (lib "General_Library") (part "CMP-019-0006"))
    )
    (comp (ref "TP19")
      (value "TP_SMT_1MM_CIR")
      (footprint "TP_SMT_1.0MM_CIR")
      (description "TP SMT 1mm Circle")
      (libsource (lib "General_Library") (part "CMP-019-0006"))
    )
    (comp (ref "TP20")
      (value "TP_SMT_1MM_CIR")
      (footprint "TP_SMT_1.0MM_CIR")
      (description "TP SMT 1mm Circle")
      (libsource (lib "General_Library") (part "CMP-019-0006"))
    )
    (comp (ref "TP21")
      (value "TP_SMT_1MM_CIR")
      (footprint "TP_SMT_1.0MM_CIR")
      (description "TP SMT 1mm Circle")
      (libsource (lib "General_Library") (part "CMP-019-0006"))
    )
    (comp (ref "TP22")
      (value "TP_SMT_1MM_CIR")
      (footprint "TP_SMT_1.0MM_CIR")
      (description "TP SMT 1mm Circle")
      (libsource (lib "General_Library") (part "CMP-019-0006"))
    )
    (comp (ref "TP23")
      (value "TP_SMT_1MM_CIR")
      (footprint "TP_SMT_1.0MM_CIR")
      (description "TP SMT 1mm Circle")
      (libsource (lib "General_Library") (part "CMP-019-0006"))
    )
    (comp (ref "TP24")
      (value "TP_SMT_1MM_CIR")
      (footprint "TP_SMT_1.0MM_CIR")
      (description "TP SMT 1mm Circle")
      (libsource (lib "General_Library") (part "CMP-019-0006"))
    )
    (comp (ref "TP25")
      (value "TP_SMT_1MM_CIR")
      (footprint "TP_SMT_1.0MM_CIR")
      (description "TP SMT 1mm Circle")
      (libsource (lib "General_Library") (part "CMP-019-0006"))
    )
    (comp (ref "TP26")
      (value "TP_SMT_1MM_CIR")
      (footprint "TP_SMT_1.0MM_CIR")
      (description "TP SMT 1mm Circle")
      (libsource (lib "General_Library") (part "CMP-019-0006"))
    )
    (comp (ref "TP27")
      (value "TP_SMT_1MM_CIR")
      (footprint "TP_SMT_1.0MM_CIR")
      (description "TP SMT 1mm Circle")
      (libsource (lib "General_Library") (part "CMP-019-0006"))
    )
    (comp (ref "TP28")
      (value "TP_SMT_1MM_CIR")
      (footprint "TP_SMT_1.0MM_CIR")
      (description "TP SMT 1mm Circle")
      (libsource (lib "General_Library") (part "CMP-019-0006"))
    )
    (comp (ref "TP29")
      (value "TP_SMT_1MM_CIR")
      (footprint "TP_SMT_1.0MM_CIR")
      (description "TP SMT 1mm Circle")
      (libsource (lib "General_Library") (part "CMP-019-0006"))
    )
    (comp (ref "TP30")
      (value "TP_SMT_1MM_CIR")
      (footprint "TP_SMT_1.0MM_CIR")
      (description "TP SMT 1mm Circle")
      (libsource (lib "General_Library") (part "CMP-019-0006"))
    )
    (comp (ref "TP31")
      (value "TP_SMT_1MM_CIR")
      (footprint "TP_SMT_1.0MM_CIR")
      (description "TP SMT 1mm Circle")
      (libsource (lib "General_Library") (part "CMP-019-0006"))
    )
    (comp (ref "TP32")
      (value "TP_SMT_1MM_CIR")
      (footprint "TP_SMT_1.0MM_CIR")
      (description "TP SMT 1mm Circle")
      (libsource (lib "General_Library") (part "CMP-019-0006"))
    )
    (comp (ref "TP65")
      (value "TP_SMT_1MM_CIR")
      (footprint "TP_SMT_1.0MM_CIR")
      (description "TP SMT 1mm Circle")
      (libsource (lib "General_Library") (part "CMP-019-0006"))
    )
    (comp (ref "TP66")
      (value "TP_SMT_1MM_CIR")
      (footprint "TP_SMT_1.0MM_CIR")
      (description "TP SMT 1mm Circle")
      (libsource (lib "General_Library") (part "CMP-019-0006"))
    )
    (comp (ref "TP67")
      (value "TP_SMT_1MM_CIR")
      (footprint "TP_SMT_1.0MM_CIR")
      (description "TP SMT 1mm Circle")
      (libsource (lib "General_Library") (part "CMP-019-0006"))
    )
    (comp (ref "TP68")
      (value "TP_SMT_1MM_CIR")
      (footprint "TP_SMT_1.0MM_CIR")
      (description "TP SMT 1mm Circle")
      (libsource (lib "General_Library") (part "CMP-019-0006"))
    )
    (comp (ref "TP69")
      (value "TP_SMT_1MM_CIR")
      (footprint "TP_SMT_1.0MM_CIR")
      (description "TP SMT 1mm Circle")
      (libsource (lib "General_Library") (part "CMP-019-0006"))
    )
    (comp (ref "TP70")
      (value "TP_SMT_1MM_CIR")
      (footprint "TP_SMT_1.0MM_CIR")
      (description "TP SMT 1mm Circle")
      (libsource (lib "General_Library") (part "CMP-019-0006"))
    )
    (comp (ref "TP71")
      (value "TP_SMT_1MM_CIR")
      (footprint "TP_SMT_1.0MM_CIR")
      (description "TP SMT 1mm Circle")
      (libsource (lib "General_Library") (part "CMP-019-0006"))
    )
    (comp (ref "TP72")
      (value "TP_SMT_1MM_CIR")
      (footprint "TP_SMT_1.0MM_CIR")
      (description "TP SMT 1mm Circle")
      (libsource (lib "General_Library") (part "CMP-019-0006"))
    )
    (comp (ref "TP73")
      (value "TP_SMT_1MM_CIR")
      (footprint "TP_SMT_1.0MM_CIR")
      (description "TP SMT 1mm Circle")
      (libsource (lib "General_Library") (part "CMP-019-0006"))
    )
    (comp (ref "TP74")
      (value "TP_SMT_1MM_CIR")
      (footprint "TP_SMT_1.0MM_CIR")
      (description "TP SMT 1mm Circle")
      (libsource (lib "General_Library") (part "CMP-019-0006"))
    )
    (comp (ref "TP75")
      (value "TP_SMT_1MM_CIR")
      (footprint "TP_SMT_1.0MM_CIR")
      (description "TP SMT 1mm Circle")
      (libsource (lib "General_Library") (part "CMP-019-0006"))
    )
    (comp (ref "TP76")
      (value "TP_SMT_1MM_CIR")
      (footprint "TP_SMT_1.0MM_CIR")
      (description "TP SMT 1mm Circle")
      (libsource (lib "General_Library") (part "CMP-019-0006"))
    )
    (comp (ref "TP77")
      (value "TP_SMT_1MM_CIR")
      (footprint "TP_SMT_1.0MM_CIR")
      (description "TP SMT 1mm Circle")
      (libsource (lib "General_Library") (part "CMP-019-0006"))
    )
    (comp (ref "TP78")
      (value "TP_SMT_1MM_CIR")
      (footprint "TP_SMT_1.0MM_CIR")
      (description "TP SMT 1mm Circle")
      (libsource (lib "General_Library") (part "CMP-019-0006"))
    )
    (comp (ref "TP79")
      (value "TP_SMT_1MM_CIR")
      (footprint "TP_SMT_1.0MM_CIR")
      (description "TP SMT 1mm Circle")
      (libsource (lib "General_Library") (part "CMP-019-0006"))
    )
    (comp (ref "TP80")
      (value "TP_SMT_1MM_CIR")
      (footprint "TP_SMT_1.0MM_CIR")
      (description "TP SMT 1mm Circle")
      (libsource (lib "General_Library") (part "CMP-019-0006"))
    )
    (comp (ref "TP81")
      (value "TP_SMT_1MM_CIR")
      (footprint "TP_SMT_1.0MM_CIR")
      (description "TP SMT 1mm Circle")
      (libsource (lib "General_Library") (part "CMP-019-0006"))
    )
    (comp (ref "TP82")
      (value "TP_SMT_1MM_CIR")
      (footprint "TP_SMT_1.0MM_CIR")
      (description "TP SMT 1mm Circle")
      (libsource (lib "General_Library") (part "CMP-019-0006"))
    )
    (comp (ref "TP83")
      (value "TP_SMT_1MM_CIR")
      (footprint "TP_SMT_1.0MM_CIR")
      (description "TP SMT 1mm Circle")
      (libsource (lib "General_Library") (part "CMP-019-0006"))
    )
    (comp (ref "TP84")
      (value "TP_SMT_1MM_CIR")
      (footprint "TP_SMT_1.0MM_CIR")
      (description "TP SMT 1mm Circle")
      (libsource (lib "General_Library") (part "CMP-019-0006"))
    )
    (comp (ref "TP85")
      (value "TP_SMT_1MM_CIR")
      (footprint "TP_SMT_1.0MM_CIR")
      (description "TP SMT 1mm Circle")
      (libsource (lib "General_Library") (part "CMP-019-0006"))
    )
    (comp (ref "TP86")
      (value "TP_SMT_1MM_CIR")
      (footprint "TP_SMT_1.0MM_CIR")
      (description "TP SMT 1mm Circle")
      (libsource (lib "General_Library") (part "CMP-019-0006"))
    )
    (comp (ref "TP87")
      (value "TP_SMT_1MM_CIR")
      (footprint "TP_SMT_1.0MM_CIR")
      (description "TP SMT 1mm Circle")
      (libsource (lib "General_Library") (part "CMP-019-0006"))
    )
    (comp (ref "TP88")
      (value "TP_SMT_1MM_CIR")
      (footprint "TP_SMT_1.0MM_CIR")
      (description "TP SMT 1mm Circle")
      (libsource (lib "General_Library") (part "CMP-019-0006"))
    )
    (comp (ref "TP89")
      (value "TP_SMT_1MM_CIR")
      (footprint "TP_SMT_1.0MM_CIR")
      (description "TP SMT 1mm Circle")
      (libsource (lib "General_Library") (part "CMP-019-0006"))
    )
    (comp (ref "TP90")
      (value "TP_SMT_1MM_CIR")
      (footprint "TP_SMT_1.0MM_CIR")
      (description "TP SMT 1mm Circle")
      (libsource (lib "General_Library") (part "CMP-019-0006"))
    )
    (comp (ref "TP91")
      (value "TP_SMT_1MM_CIR")
      (footprint "TP_SMT_1.0MM_CIR")
      (description "TP SMT 1mm Circle")
      (libsource (lib "General_Library") (part "CMP-019-0006"))
    )
    (comp (ref "TP92")
      (value "TP_SMT_1MM_CIR")
      (footprint "TP_SMT_1.0MM_CIR")
      (description "TP SMT 1mm Circle")
      (libsource (lib "General_Library") (part "CMP-019-0006"))
    )
    (comp (ref "TP93")
      (value "TP_SMT_1MM_CIR")
      (footprint "TP_SMT_1.0MM_CIR")
      (description "TP SMT 1mm Circle")
      (libsource (lib "General_Library") (part "CMP-019-0006"))
    )
    (comp (ref "TP94")
      (value "TP_SMT_1MM_CIR")
      (footprint "TP_SMT_1.0MM_CIR")
      (description "TP SMT 1mm Circle")
      (libsource (lib "General_Library") (part "CMP-019-0006"))
    )
    (comp (ref "TP95")
      (value "TP_SMT_1MM_CIR")
      (footprint "TP_SMT_1.0MM_CIR")
      (description "TP SMT 1mm Circle")
      (libsource (lib "General_Library") (part "CMP-019-0006"))
    )
    (comp (ref "TP96")
      (value "TP_SMT_1MM_CIR")
      (footprint "TP_SMT_1.0MM_CIR")
      (description "TP SMT 1mm Circle")
      (libsource (lib "General_Library") (part "CMP-019-0006"))
    )
  )
  (nets
    (net (code "17") (name "/I2C_MUX_SCL0") (class "Default")
      (node (ref "R129") (pin "1") (pinfunction "1_1") (pintype "passive"))
      (node (ref "R130") (pin "1") (pinfunction "1_1") (pintype "passive"))
      (node (ref "R132") (pin "1") (pinfunction "1_1") (pintype "passive"))
      (node (ref "R156") (pin "1") (pinfunction "1_1") (pintype "passive"))
      (node (ref "R157") (pin "1") (pinfunction "1_1") (pintype "passive"))
      (node (ref "R159") (pin "1") (pinfunction "1_1") (pintype "passive"))
      (node (ref "R179") (pin "1") (pinfunction "1_1") (pintype "passive"))
      (node (ref "R180") (pin "1") (pinfunction "1_1") (pintype "passive"))
      (node (ref "TC10") (pin "19") (pinfunction "SCL_19") (pintype "passive"))
      (node (ref "TC11") (pin "19") (pinfunction "SCL_19") (pintype "passive"))
      (node (ref "TC12") (pin "19") (pinfunction "SCL_19") (pintype "passive"))
      (node (ref "TC13") (pin "19") (pinfunction "SCL_19") (pintype "passive"))
      (node (ref "TC14") (pin "19") (pinfunction "SCL_19") (pintype "passive"))
      (node (ref "TC15") (pin "19") (pinfunction "SCL_19") (pintype "passive"))
      (node (ref "TC16") (pin "19") (pinfunction "SCL_19") (pintype "passive"))
      (node (ref "TC9") (pin "19") (pinfunction "SCL_19") (pintype "passive"))
    )
    (net (code "18") (name "/I2C_MUX_SDA0") (class "Default")
      (node (ref "R133") (pin "1") (pinfunction "1_1") (pintype "passive"))
      (node (ref "R134") (pin "1") (pinfunction "1_1") (pintype "passive"))
      (node (ref "R135") (pin "1") (pinfunction "1_1") (pintype "passive"))
      (node (ref "R160") (pin "1") (pinfunction "1_1") (pintype "passive"))
      (node (ref "R161") (pin "1") (pinfunction "1_1") (pintype "passive"))
      (node (ref "R166") (pin "1") (pinfunction "1_1") (pintype "passive"))
      (node (ref "R181") (pin "1") (pinfunction "1_1") (pintype "passive"))
      (node (ref "R182") (pin "1") (pinfunction "1_1") (pintype "passive"))
      (node (ref "TC10") (pin "20") (pinfunction "SDA_20") (pintype "passive"))
      (node (ref "TC11") (pin "20") (pinfunction "SDA_20") (pintype "passive"))
      (node (ref "TC12") (pin "20") (pinfunction "SDA_20") (pintype "passive"))
      (node (ref "TC13") (pin "20") (pinfunction "SDA_20") (pintype "passive"))
      (node (ref "TC14") (pin "20") (pinfunction "SDA_20") (pintype "passive"))
      (node (ref "TC15") (pin "20") (pinfunction "SDA_20") (pintype "passive"))
      (node (ref "TC16") (pin "20") (pinfunction "SDA_20") (pintype "passive"))
      (node (ref "TC9") (pin "20") (pinfunction "SDA_20") (pintype "passive"))
    )
    (net (code "19") (name "/TC_NEG9") (class "Default")
      (node (ref "R141") (pin "2") (pinfunction "2_2") (pintype "passive"))
    )
    (net (code "20") (name "/TC_NEG10") (class "Default")
      (node (ref "R137") (pin "2") (pinfunction "2_2") (pintype "passive"))
    )
    (net (code "21") (name "/TC_NEG11") (class "Default")
      (node (ref "R139") (pin "2") (pinfunction "2_2") (pintype "passive"))
    )
    (net (code "22") (name "/TC_NEG12") (class "Default")
      (node (ref "R168") (pin "2") (pinfunction "2_2") (pintype "passive"))
    )
    (net (code "23") (name "/TC_NEG13") (class "Default")
      (node (ref "R163") (pin "2") (pinfunction "2_2") (pintype "passive"))
    )
    (net (code "24") (name "/TC_NEG14") (class "Default")
      (node (ref "R165") (pin "2") (pinfunction "2_2") (pintype "passive"))
    )
    (net (code "25") (name "/TC_NEG15") (class "Default")
      (node (ref "R184") (pin "2") (pinfunction "2_2") (pintype "passive"))
    )
    (net (code "26") (name "/TC_NEG16") (class "Default")
      (node (ref "R186") (pin "2") (pinfunction "2_2") (pintype "passive"))
    )
    (net (code "28") (name "/TC_POS9") (class "Default")
      (node (ref "R140") (pin "2") (pinfunction "2_2") (pintype "passive"))
    )
    (net (code "29") (name "/TC_POS10") (class "Default")
      (node (ref "R136") (pin "2") (pinfunction "2_2") (pintype "passive"))
    )
    (net (code "30") (name "/TC_POS11") (class "Default")
      (node (ref "R138") (pin "2") (pinfunction "2_2") (pintype "passive"))
    )
    (net (code "31") (name "/TC_POS12") (class "Default")
      (node (ref "R167") (pin "2") (pinfunction "2_2") (pintype "passive"))
    )
    (net (code "32") (name "/TC_POS13") (class "Default")
      (node (ref "R162") (pin "2") (pinfunction "2_2") (pintype "passive"))
    )
    (net (code "33") (name "/TC_POS14") (class "Default")
      (node (ref "R164") (pin "2") (pinfunction "2_2") (pintype "passive"))
    )
    (net (code "34") (name "/TC_POS15") (class "Default")
      (node (ref "R183") (pin "2") (pinfunction "2_2") (pintype "passive"))
    )
    (net (code "35") (name "/TC_POS16") (class "Default")
      (node (ref "R185") (pin "2") (pinfunction "2_2") (pintype "passive"))
    )
    (net (code "37") (name "GND") (class "Default")
      (node (ref "C58") (pin "2") (pinfunction "2_2") (pintype "passive"))
      (node (ref "C59") (pin "2") (pinfunction "2_2") (pintype "passive"))
      (node (ref "C60") (pin "2") (pinfunction "2_2") (pintype "passive"))
      (node (ref "C64") (pin "2") (pinfunction "2_2") (pintype "passive"))
      (node (ref "C65") (pin "2") (pinfunction "2_2") (pintype "passive"))
      (node (ref "C66") (pin "2") (pinfunction "2_2") (pintype "passive"))
      (node (ref "C70") (pin "2") (pinfunction "2_2") (pintype "passive"))
      (node (ref "C71") (pin "2") (pinfunction "2_2") (pintype "passive"))
      (node (ref "R115") (pin "1") (pinfunction "1_1") (pintype "passive"))
      (node (ref "R116") (pin "1") (pinfunction "1_1") (pintype "passive"))
      (node (ref "R117") (pin "1") (pinfunction "1_1") (pintype "passive"))
      (node (ref "R118") (pin "1") (pinfunction "1_1") (pintype "passive"))
      (node (ref "R119") (pin "1") (pinfunction "1_1") (pintype "passive"))
      (node (ref "R120") (pin "1") (pinfunction "1_1") (pintype "passive"))
      (node (ref "R121") (pin "1") (pinfunction "1_1") (pintype "passive"))
      (node (ref "R122") (pin "1") (pinfunction "1_1") (pintype "passive"))
      (node (ref "R123") (pin "1") (pinfunction "1_1") (pintype "passive"))
      (node (ref "R142") (pin "1") (pinfunction "1_1") (pintype "passive"))
      (node (ref "R143") (pin "1") (pinfunction "1_1") (pintype "passive"))
      (node (ref "R144") (pin "1") (pinfunction "1_1") (pintype "passive"))
      (node (ref "R145") (pin "1") (pinfunction "1_1") (pintype "passive"))
      (node (ref "R146") (pin "1") (pinfunction "1_1") (pintype "passive"))
      (node (ref "R147") (pin "1") (pinfunction "1_1") (pintype "passive"))
      (node (ref "R148") (pin "1") (pinfunction "1_1") (pintype "passive"))
      (node (ref "R149") (pin "1") (pinfunction "1_1") (pintype "passive"))
      (node (ref "R150") (pin "1") (pinfunction "1_1") (pintype "passive"))
      (node (ref "R169") (pin "1") (pinfunction "1_1") (pintype "passive"))
      (node (ref "R170") (pin "1") (pinfunction "1_1") (pintype "passive"))
      (node (ref "R171") (pin "1") (pinfunction "1_1") (pintype "passive"))
      (node (ref "R172") (pin "1") (pinfunction "1_1") (pintype "passive"))
      (node (ref "R173") (pin "1") (pinfunction "1_1") (pintype "passive"))
      (node (ref "R174") (pin "1") (pinfunction "1_1") (pintype "passive"))
      (node (ref "TC10") (pin "1") (pinfunction "GND_1") (pintype "power_in"))
      (node (ref "TC10") (pin "10") (pinfunction "GND_10") (pintype "power_in"))
      (node (ref "TC10") (pin "13") (pinfunction "GND_13") (pintype "power_in"))
      (node (ref "TC10") (pin "17") (pinfunction "GND_17") (pintype "power_in"))
      (node (ref "TC10") (pin "18") (pinfunction "GND_18") (pintype "power_in"))
      (node (ref "TC10") (pin "21") (pinfunction "EP_21") (pintype "passive"))
      (node (ref "TC10") (pin "3") (pinfunction "GND_3") (pintype "power_in"))
      (node (ref "TC10") (pin "5") (pinfunction "GND_5") (pintype "power_in"))
      (node (ref "TC11") (pin "1") (pinfunction "GND_1") (pintype "power_in"))
      (node (ref "TC11") (pin "10") (pinfunction "GND_10") (pintype "power_in"))
      (node (ref "TC11") (pin "13") (pinfunction "GND_13") (pintype "power_in"))
      (node (ref "TC11") (pin "17") (pinfunction "GND_17") (pintype "power_in"))
      (node (ref "TC11") (pin "18") (pinfunction "GND_18") (pintype "power_in"))
      (node (ref "TC11") (pin "21") (pinfunction "EP_21") (pintype "passive"))
      (node (ref "TC11") (pin "3") (pinfunction "GND_3") (pintype "power_in"))
      (node (ref "TC11") (pin "5") (pinfunction "GND_5") (pintype "power_in"))
      (node (ref "TC12") (pin "1") (pinfunction "GND_1") (pintype "power_in"))
      (node (ref "TC12") (pin "10") (pinfunction "GND_10") (pintype "power_in"))
      (node (ref "TC12") (pin "13") (pinfunction "GND_13") (pintype "power_in"))
      (node (ref "TC12") (pin "17") (pinfunction "GND_17") (pintype "power_in"))
      (node (ref "TC12") (pin "18") (pinfunction "GND_18") (pintype "power_in"))
      (node (ref "TC12") (pin "21") (pinfunction "EP_21") (pintype "passive"))
      (node (ref "TC12") (pin "3") (pinfunction "GND_3") (pintype "power_in"))
      (node (ref "TC12") (pin "5") (pinfunction "GND_5") (pintype "power_in"))
      (node (ref "TC13") (pin "1") (pinfunction "GND_1") (pintype "power_in"))
      (node (ref "TC13") (pin "10") (pinfunction "GND_10") (pintype "power_in"))
      (node (ref "TC13") (pin "13") (pinfunction "GND_13") (pintype "power_in"))
      (node (ref "TC13") (pin "17") (pinfunction "GND_17") (pintype "power_in"))
      (node (ref "TC13") (pin "18") (pinfunction "GND_18") (pintype "power_in"))
      (node (ref "TC13") (pin "21") (pinfunction "EP_21") (pintype "passive"))
      (node (ref "TC13") (pin "3") (pinfunction "GND_3") (pintype "power_in"))
      (node (ref "TC13") (pin "5") (pinfunction "GND_5") (pintype "power_in"))
      (node (ref "TC14") (pin "1") (pinfunction "GND_1") (pintype "power_in"))
      (node (ref "TC14") (pin "10") (pinfunction "GND_10") (pintype "power_in"))
      (node (ref "TC14") (pin "13") (pinfunction "GND_13") (pintype "power_in"))
      (node (ref "TC14") (pin "17") (pinfunction "GND_17") (pintype "power_in"))
      (node (ref "TC14") (pin "18") (pinfunction "GND_18") (pintype "power_in"))
      (node (ref "TC14") (pin "21") (pinfunction "EP_21") (pintype "passive"))
      (node (ref "TC14") (pin "3") (pinfunction "GND_3") (pintype "power_in"))
      (node (ref "TC14") (pin "5") (pinfunction "GND_5") (pintype "power_in"))
      (node (ref "TC15") (pin "1") (pinfunction "GND_1") (pintype "power_in"))
      (node (ref "TC15") (pin "10") (pinfunction "GND_10") (pintype "power_in"))
      (node (ref "TC15") (pin "13") (pinfunction "GND_13") (pintype "power_in"))
      (node (ref "TC15") (pin "17") (pinfunction "GND_17") (pintype "power_in"))
      (node (ref "TC15") (pin "18") (pinfunction "GND_18") (pintype "power_in"))
      (node (ref "TC15") (pin "21") (pinfunction "EP_21") (pintype "passive"))
      (node (ref "TC15") (pin "3") (pinfunction "GND_3") (pintype "power_in"))
      (node (ref "TC15") (pin "5") (pinfunction "GND_5") (pintype "power_in"))
      (node (ref "TC16") (pin "1") (pinfunction "GND_1") (pintype "power_in"))
      (node (ref "TC16") (pin "10") (pinfunction "GND_10") (pintype "power_in"))
      (node (ref "TC16") (pin "13") (pinfunction "GND_13") (pintype "power_in"))
      (node (ref "TC16") (pin "17") (pinfunction "GND_17") (pintype "power_in"))
      (node (ref "TC16") (pin "18") (pinfunction "GND_18") (pintype "power_in"))
      (node (ref "TC16") (pin "21") (pinfunction "EP_21") (pintype "passive"))
      (node (ref "TC16") (pin "3") (pinfunction "GND_3") (pintype "power_in"))
      (node (ref "TC16") (pin "5") (pinfunction "GND_5") (pintype "power_in"))
      (node (ref "TC9") (pin "1") (pinfunction "GND_1") (pintype "power_in"))
      (node (ref "TC9") (pin "10") (pinfunction "GND_10") (pintype "power_in"))
      (node (ref "TC9") (pin "13") (pinfunction "GND_13") (pintype "power_in"))
      (node (ref "TC9") (pin "17") (pinfunction "GND_17") (pintype "power_in"))
      (node (ref "TC9") (pin "18") (pinfunction "GND_18") (pintype "power_in"))
      (node (ref "TC9") (pin "21") (pinfunction "EP_21") (pintype "passive"))
      (node (ref "TC9") (pin "3") (pinfunction "GND_3") (pintype "power_in"))
      (node (ref "TC9") (pin "5") (pinfunction "GND_5") (pintype "power_in"))
    )
    (net (code "38") (name "Net-(TC9-ADDR)") (class "Default")
      (node (ref "R120") (pin "2") (pinfunction "2_2") (pintype "passive"))
      (node (ref "R126") (pin "1") (pinfunction "1_1") (pintype "passive"))
      (node (ref "TC9") (pin "16") (pinfunction "ADDR_16") (pintype "passive"))
    )
    (net (code "39") (name "Net-(TC9-ALERT1)") (class "Default")
      (node (ref "TC9") (pin "11") (pinfunction "ALERT1_11") (pintype "passive"))
      (node (ref "TP76") (pin "1") (pinfunction "1_1") (pintype "passive"))
    )
    (net (code "40") (name "Net-(TC9-ALERT2)") (class "Default")
      (node (ref "TC9") (pin "12") (pinfunction "ALERT2_12") (pintype "passive"))
      (node (ref "TP75") (pin "1") (pinfunction "1_1") (pintype "passive"))
    )
    (net (code "41") (name "Net-(TC9-ALERT3)") (class "Default")
      (node (ref "TC9") (pin "14") (pinfunction "ALERT3_14") (pintype "passive"))
      (node (ref "TP74") (pin "1") (pinfunction "1_1") (pintype "passive"))
    )
    (net (code "42") (name "Net-(TC9-ALERT4)") (class "Default")
      (node (ref "TC9") (pin "15") (pinfunction "ALERT4_15") (pintype "passive"))
      (node (ref "TP73") (pin "1") (pinfunction "1_1") (pintype "passive"))
    )
    (net (code "43") (name "Net-(TC9-OC_ALERT)") (class "Default")
      (node (ref "TC9") (pin "9") (pinfunction "OC_ALERT_9") (pintype "passive"))
      (node (ref "TP22") (pin "1") (pinfunction "1_1") (pintype "passive"))
    )
    (net (code "44") (name "Net-(TC9-SC_ALERT)") (class "Default")
      (node (ref "TC9") (pin "7") (pinfunction "SC_ALERT_7") (pintype "passive"))
      (node (ref "TP21") (pin "1") (pinfunction "1_1") (pintype "passive"))
    )
    (net (code "45") (name "Net-(TC9-VIN+)") (class "Default")
      (node (ref "C63") (pin "1") (pinfunction "1_1") (pintype "passive"))
      (node (ref "R123") (pin "2") (pinfunction "2_2") (pintype "passive"))
      (node (ref "R131") (pin "1") (pinfunction "1_1") (pintype "passive"))
      (node (ref "R140") (pin "1") (pinfunction "1_1") (pintype "passive"))
      (node (ref "TC9") (pin "2") (pinfunction "VIN+_2") (pintype "passive"))
      (node (ref "TC9") (pin "6") (pinfunction "V_SENSE_6") (pintype "passive"))
    )
    (net (code "46") (name "Net-(TC9-VIN-)") (class "Default")
      (node (ref "C63") (pin "2") (pinfunction "2_2") (pintype "passive"))
      (node (ref "R117") (pin "2") (pinfunction "2_2") (pintype "passive"))
      (node (ref "R141") (pin "1") (pinfunction "1_1") (pintype "passive"))
      (node (ref "TC9") (pin "4") (pinfunction "VIN-_4") (pintype "passive"))
    )
    (net (code "47") (name "Net-(TC10-ADDR)") (class "Default")
      (node (ref "R118") (pin "2") (pinfunction "2_2") (pintype "passive"))
      (node (ref "R124") (pin "1") (pinfunction "1_1") (pintype "passive"))
      (node (ref "TC10") (pin "16") (pinfunction "ADDR_16") (pintype "passive"))
    )
    (net (code "48") (name "Net-(TC10-ALERT1)") (class "Default")
      (node (ref "TC10") (pin "11") (pinfunction "ALERT1_11") (pintype "passive"))
      (node (ref "TP68") (pin "1") (pinfunction "1_1") (pintype "passive"))
    )
    (net (code "49") (name "Net-(TC10-ALERT2)") (class "Default")
      (node (ref "TC10") (pin "12") (pinfunction "ALERT2_12") (pintype "passive"))
      (node (ref "TP67") (pin "1") (pinfunction "1_1") (pintype "passive"))
    )
    (net (code "50") (name "Net-(TC10-ALERT3)") (class "Default")
      (node (ref "TC10") (pin "14") (pinfunction "ALERT3_14") (pintype "passive"))
      (node (ref "TP66") (pin "1") (pinfunction "1_1") (pintype "passive"))
    )
    (net (code "51") (name "Net-(TC10-ALERT4)") (class "Default")
      (node (ref "TC10") (pin "15") (pinfunction "ALERT4_15") (pintype "passive"))
      (node (ref "TP65") (pin "1") (pinfunction "1_1") (pintype "passive"))
    )
    (net (code "52") (name "Net-(TC10-OC_ALERT)") (class "Default")
      (node (ref "TC10") (pin "9") (pinfunction "OC_ALERT_9") (pintype "passive"))
      (node (ref "TP18") (pin "1") (pinfunction "1_1") (pintype "passive"))
    )
    (net (code "53") (name "Net-(TC10-SC_ALERT)") (class "Default")
      (node (ref "TC10") (pin "7") (pinfunction "SC_ALERT_7") (pintype "passive"))
      (node (ref "TP17") (pin "1") (pinfunction "1_1") (pintype "passive"))
    )
    (net (code "54") (name "Net-(TC10-VIN+)") (class "Default")
      (node (ref "C61") (pin "1") (pinfunction "1_1") (pintype "passive"))
      (node (ref "R121") (pin "2") (pinfunction "2_2") (pintype "passive"))
      (node (ref "R127") (pin "1") (pinfunction "1_1") (pintype "passive"))
      (node (ref "R136") (pin "1") (pinfunction "1_1") (pintype "passive"))
      (node (ref "TC10") (pin "2") (pinfunction "VIN+_2") (pintype "passive"))
      (node (ref "TC10") (pin "6") (pinfunction "V_SENSE_6") (pintype "passive"))
    )
    (net (code "55") (name "Net-(TC10-VIN-)") (class "Default")
      (node (ref "C61") (pin "2") (pinfunction "2_2") (pintype "passive"))
      (node (ref "R115") (pin "2") (pinfunction "2_2") (pintype "passive"))
      (node (ref "R137") (pin "1") (pinfunction "1_1") (pintype "passive"))
      (node (ref "TC10") (pin "4") (pinfunction "VIN-_4") (pintype "passive"))
    )
    (net (code "56") (name "Net-(TC11-ADDR)") (class "Default")
      (node (ref "R119") (pin "2") (pinfunction "2_2") (pintype "passive"))
      (node (ref "R125") (pin "1") (pinfunction "1_1") (pintype "passive"))
      (node (ref "TC11") (pin "16") (pinfunction "ADDR_16") (pintype "passive"))
    )
    (net (code "57") (name "Net-(TC11-ALERT1)") (class "Default")
      (node (ref "TC11") (pin "11") (pinfunction "ALERT1_11") (pintype "passive"))
      (node (ref "TP72") (pin "1") (pinfunction "1_1") (pintype "passive"))
    )
    (net (code "58") (name "Net-(TC11-ALERT2)") (class "Default")
      (node (ref "TC11") (pin "12") (pinfunction "ALERT2_12") (pintype "passive"))
      (node (ref "TP71") (pin "1") (pinfunction "1_1") (pintype "passive"))
    )
    (net (code "59") (name "Net-(TC11-ALERT3)") (class "Default")
      (node (ref "TC11") (pin "14") (pinfunction "ALERT3_14") (pintype "passive"))
      (node (ref "TP70") (pin "1") (pinfunction "1_1") (pintype "passive"))
    )
    (net (code "60") (name "Net-(TC11-ALERT4)") (class "Default")
      (node (ref "TC11") (pin "15") (pinfunction "ALERT4_15") (pintype "passive"))
      (node (ref "TP69") (pin "1") (pinfunction "1_1") (pintype "passive"))
    )
    (net (code "61") (name "Net-(TC11-OC_ALERT)") (class "Default")
      (node (ref "TC11") (pin "9") (pinfunction "OC_ALERT_9") (pintype "passive"))
      (node (ref "TP20") (pin "1") (pinfunction "1_1") (pintype "passive"))
    )
    (net (code "62") (name "Net-(TC11-SC_ALERT)") (class "Default")
      (node (ref "TC11") (pin "7") (pinfunction "SC_ALERT_7") (pintype "passive"))
      (node (ref "TP19") (pin "1") (pinfunction "1_1") (pintype "passive"))
    )
    (net (code "63") (name "Net-(TC11-VIN+)") (class "Default")
      (node (ref "C62") (pin "1") (pinfunction "1_1") (pintype "passive"))
      (node (ref "R122") (pin "2") (pinfunction "2_2") (pintype "passive"))
      (node (ref "R128") (pin "1") (pinfunction "1_1") (pintype "passive"))
      (node (ref "R138") (pin "1") (pinfunction "1_1") (pintype "passive"))
      (node (ref "TC11") (pin "2") (pinfunction "VIN+_2") (pintype "passive"))
      (node (ref "TC11") (pin "6") (pinfunction "V_SENSE_6") (pintype "passive"))
    )
    (net (code "64") (name "Net-(TC11-VIN-)") (class "Default")
      (node (ref "C62") (pin "2") (pinfunction "2_2") (pintype "passive"))
      (node (ref "R116") (pin "2") (pinfunction "2_2") (pintype "passive"))
      (node (ref "R139") (pin "1") (pinfunction "1_1") (pintype "passive"))
      (node (ref "TC11") (pin "4") (pinfunction "VIN-_4") (pintype "passive"))
    )
    (net (code "65") (name "Net-(TC12-ADDR)") (class "Default")
      (node (ref "R147") (pin "2") (pinfunction "2_2") (pintype "passive"))
      (node (ref "R153") (pin "1") (pinfunction "1_1") (pintype "passive"))
      (node (ref "TC12") (pin "16") (pinfunction "ADDR_16") (pintype "passive"))
    )
    (net (code "66") (name "Net-(TC12-ALERT1)") (class "Default")
      (node (ref "TC12") (pin "11") (pinfunction "ALERT1_11") (pintype "passive"))
      (node (ref "TP88") (pin "1") (pinfunction "1_1") (pintype "passive"))
    )
    (net (code "67") (name "Net-(TC12-ALERT2)") (class "Default")
      (node (ref "TC12") (pin "12") (pinfunction "ALERT2_12") (pintype "passive"))
      (node (ref "TP87") (pin "1") (pinfunction "1_1") (pintype "passive"))
    )
    (net (code "68") (name "Net-(TC12-ALERT3)") (class "Default")
      (node (ref "TC12") (pin "14") (pinfunction "ALERT3_14") (pintype "passive"))
      (node (ref "TP86") (pin "1") (pinfunction "1_1") (pintype "passive"))
    )
    (net (code "69") (name "Net-(TC12-ALERT4)") (class "Default")
      (node (ref "TC12") (pin "15") (pinfunction "ALERT4_15") (pintype "passive"))
      (node (ref "TP85") (pin "1") (pinfunction "1_1") (pintype "passive"))
    )
    (net (code "70") (name "Net-(TC12-OC_ALERT)") (class "Default")
      (node (ref "TC12") (pin "9") (pinfunction "OC_ALERT_9") (pintype "passive"))
      (node (ref "TP28") (pin "1") (pinfunction "1_1") (pintype "passive"))
    )
    (net (code "71") (name "Net-(TC12-SC_ALERT)") (class "Default")
      (node (ref "TC12") (pin "7") (pinfunction "SC_ALERT_7") (pintype "passive"))
      (node (ref "TP27") (pin "1") (pinfunction "1_1") (pintype "passive"))
    )
    (net (code "72") (name "Net-(TC12-VIN+)") (class "Default")
      (node (ref "C69") (pin "1") (pinfunction "1_1") (pintype "passive"))
      (node (ref "R150") (pin "2") (pinfunction "2_2") (pintype "passive"))
      (node (ref "R158") (pin "1") (pinfunction "1_1") (pintype "passive"))
      (node (ref "R167") (pin "1") (pinfunction "1_1") (pintype "passive"))
      (node (ref "TC12") (pin "2") (pinfunction "VIN+_2") (pintype "passive"))
      (node (ref "TC12") (pin "6") (pinfunction "V_SENSE_6") (pintype "passive"))
    )
    (net (code "73") (name "Net-(TC12-VIN-)") (class "Default")
      (node (ref "C69") (pin "2") (pinfunction "2_2") (pintype "passive"))
      (node (ref "R146") (pin "2") (pinfunction "2_2") (pintype "passive"))
      (node (ref "R168") (pin "1") (pinfunction "1_1") (pintype "passive"))
      (node (ref "TC12") (pin "4") (pinfunction "VIN-_4") (pintype "passive"))
    )
    (net (code "74") (name "Net-(TC13-ADDR)") (class "Default")
      (node (ref "R144") (pin "2") (pinfunction "2_2") (pintype "passive"))
      (node (ref "R151") (pin "1") (pinfunction "1_1") (pintype "passive"))
      (node (ref "TC13") (pin "16") (pinfunction "ADDR_16") (pintype "passive"))
    )
    (net (code "75") (name "Net-(TC13-ALERT1)") (class "Default")
      (node (ref "TC13") (pin "11") (pinfunction "ALERT1_11") (pintype "passive"))
      (node (ref "TP80") (pin "1") (pinfunction "1_1") (pintype "passive"))
    )
    (net (code "76") (name "Net-(TC13-ALERT2)") (class "Default")
      (node (ref "TC13") (pin "12") (pinfunction "ALERT2_12") (pintype "passive"))
      (node (ref "TP79") (pin "1") (pinfunction "1_1") (pintype "passive"))
    )
    (net (code "77") (name "Net-(TC13-ALERT3)") (class "Default")
      (node (ref "TC13") (pin "14") (pinfunction "ALERT3_14") (pintype "passive"))
      (node (ref "TP78") (pin "1") (pinfunction "1_1") (pintype "passive"))
    )
    (net (code "78") (name "Net-(TC13-ALERT4)") (class "Default")
      (node (ref "TC13") (pin "15") (pinfunction "ALERT4_15") (pintype "passive"))
      (node (ref "TP77") (pin "1") (pinfunction "1_1") (pintype "passive"))
    )
    (net (code "79") (name "Net-(TC13-OC_ALERT)") (class "Default")
      (node (ref "TC13") (pin "9") (pinfunction "OC_ALERT_9") (pintype "passive"))
      (node (ref "TP24") (pin "1") (pinfunction "1_1") (pintype "passive"))
    )
    (net (code "80") (name "Net-(TC13-SC_ALERT)") (class "Default")
      (node (ref "TC13") (pin "7") (pinfunction "SC_ALERT_7") (pintype "passive"))
      (node (ref "TP23") (pin "1") (pinfunction "1_1") (pintype "passive"))
    )
    (net (code "81") (name "Net-(TC13-VIN+)") (class "Default")
      (node (ref "C67") (pin "1") (pinfunction "1_1") (pintype "passive"))
      (node (ref "R148") (pin "2") (pinfunction "2_2") (pintype "passive"))
      (node (ref "R154") (pin "1") (pinfunction "1_1") (pintype "passive"))
      (node (ref "R162") (pin "1") (pinfunction "1_1") (pintype "passive"))
      (node (ref "TC13") (pin "2") (pinfunction "VIN+_2") (pintype "passive"))
      (node (ref "TC13") (pin "6") (pinfunction "V_SENSE_6") (pintype "passive"))
    )
    (net (code "82") (name "Net-(TC13-VIN-)") (class "Default")
      (node (ref "C67") (pin "2") (pinfunction "2_2") (pintype "passive"))
      (node (ref "R142") (pin "2") (pinfunction "2_2") (pintype "passive"))
      (node (ref "R163") (pin "1") (pinfunction "1_1") (pintype "passive"))
      (node (ref "TC13") (pin "4") (pinfunction "VIN-_4") (pintype "passive"))
    )
    (net (code "83") (name "Net-(TC14-ADDR)") (class "Default")
      (node (ref "R145") (pin "2") (pinfunction "2_2") (pintype "passive"))
      (node (ref "R152") (pin "1") (pinfunction "1_1") (pintype "passive"))
      (node (ref "TC14") (pin "16") (pinfunction "ADDR_16") (pintype "passive"))
    )
    (net (code "84") (name "Net-(TC14-ALERT1)") (class "Default")
      (node (ref "TC14") (pin "11") (pinfunction "ALERT1_11") (pintype "passive"))
      (node (ref "TP84") (pin "1") (pinfunction "1_1") (pintype "passive"))
    )
    (net (code "85") (name "Net-(TC14-ALERT2)") (class "Default")
      (node (ref "TC14") (pin "12") (pinfunction "ALERT2_12") (pintype "passive"))
      (node (ref "TP83") (pin "1") (pinfunction "1_1") (pintype "passive"))
    )
    (net (code "86") (name "Net-(TC14-ALERT3)") (class "Default")
      (node (ref "TC14") (pin "14") (pinfunction "ALERT3_14") (pintype "passive"))
      (node (ref "TP82") (pin "1") (pinfunction "1_1") (pintype "passive"))
    )
    (net (code "87") (name "Net-(TC14-ALERT4)") (class "Default")
      (node (ref "TC14") (pin "15") (pinfunction "ALERT4_15") (pintype "passive"))
      (node (ref "TP81") (pin "1") (pinfunction "1_1") (pintype "passive"))
    )
    (net (code "88") (name "Net-(TC14-OC_ALERT)") (class "Default")
      (node (ref "TC14") (pin "9") (pinfunction "OC_ALERT_9") (pintype "passive"))
      (node (ref "TP26") (pin "1") (pinfunction "1_1") (pintype "passive"))
    )
    (net (code "89") (name "Net-(TC14-SC_ALERT)") (class "Default")
      (node (ref "TC14") (pin "7") (pinfunction "SC_ALERT_7") (pintype "passive"))
      (node (ref "TP25") (pin "1") (pinfunction "1_1") (pintype "passive"))
    )
    (net (code "90") (name "Net-(TC14-VIN+)") (class "Default")
      (node (ref "C68") (pin "1") (pinfunction "1_1") (pintype "passive"))
      (node (ref "R149") (pin "2") (pinfunction "2_2") (pintype "passive"))
      (node (ref "R155") (pin "1") (pinfunction "1_1") (pintype "passive"))
      (node (ref "R164") (pin "1") (pinfunction "1_1") (pintype "passive"))
      (node (ref "TC14") (pin "2") (pinfunction "VIN+_2") (pintype "passive"))
      (node (ref "TC14") (pin "6") (pinfunction "V_SENSE_6") (pintype "passive"))
    )
    (net (code "91") (name "Net-(TC14-VIN-)") (class "Default")
      (node (ref "C68") (pin "2") (pinfunction "2_2") (pintype "passive"))
      (node (ref "R143") (pin "2") (pinfunction "2_2") (pintype "passive"))
      (node (ref "R165") (pin "1") (pinfunction "1_1") (pintype "passive"))
      (node (ref "TC14") (pin "4") (pinfunction "VIN-_4") (pintype "passive"))
    )
    (net (code "92") (name "Net-(TC15-ADDR)") (class "Default")
      (node (ref "R171") (pin "2") (pinfunction "2_2") (pintype "passive"))
      (node (ref "R175") (pin "1") (pinfunction "1_1") (pintype "passive"))
      (node (ref "TC15") (pin "16") (pinfunction "ADDR_16") (pintype "passive"))
    )
    (net (code "93") (name "Net-(TC15-ALERT1)") (class "Default")
      (node (ref "TC15") (pin "11") (pinfunction "ALERT1_11") (pintype "passive"))
      (node (ref "TP92") (pin "1") (pinfunction "1_1") (pintype "passive"))
    )
    (net (code "94") (name "Net-(TC15-ALERT2)") (class "Default")
      (node (ref "TC15") (pin "12") (pinfunction "ALERT2_12") (pintype "passive"))
      (node (ref "TP91") (pin "1") (pinfunction "1_1") (pintype "passive"))
    )
    (net (code "95") (name "Net-(TC15-ALERT3)") (class "Default")
      (node (ref "TC15") (pin "14") (pinfunction "ALERT3_14") (pintype "passive"))
      (node (ref "TP90") (pin "1") (pinfunction "1_1") (pintype "passive"))
    )
    (net (code "96") (name "Net-(TC15-ALERT4)") (class "Default")
      (node (ref "TC15") (pin "15") (pinfunction "ALERT4_15") (pintype "passive"))
      (node (ref "TP89") (pin "1") (pinfunction "1_1") (pintype "passive"))
    )
    (net (code "97") (name "Net-(TC15-OC_ALERT)") (class "Default")
      (node (ref "TC15") (pin "9") (pinfunction "OC_ALERT_9") (pintype "passive"))
      (node (ref "TP30") (pin "1") (pinfunction "1_1") (pintype "passive"))
    )
    (net (code "98") (name "Net-(TC15-SC_ALERT)") (class "Default")
      (node (ref "TC15") (pin "7") (pinfunction "SC_ALERT_7") (pintype "passive"))
      (node (ref "TP29") (pin "1") (pinfunction "1_1") (pintype "passive"))
    )
    (net (code "99") (name "Net-(TC15-VIN+)") (class "Default")
      (node (ref "C72") (pin "1") (pinfunction "1_1") (pintype "passive"))
      (node (ref "R173") (pin "2") (pinfunction "2_2") (pintype "passive"))
      (node (ref "R177") (pin "1") (pinfunction "1_1") (pintype "passive"))
      (node (ref "R183") (pin "1") (pinfunction "1_1") (pintype "passive"))
      (node (ref "TC15") (pin "2") (pinfunction "VIN+_2") (pintype "passive"))
      (node (ref "TC15") (pin "6") (pinfunction "V_SENSE_6") (pintype "passive"))
    )
    (net (code "100") (name "Net-(TC15-VIN-)") (class "Default")
      (node (ref "C72") (pin "2") (pinfunction "2_2") (pintype "passive"))
      (node (ref "R169") (pin "2") (pinfunction "2_2") (pintype "passive"))
      (node (ref "R184") (pin "1") (pinfunction "1_1") (pintype "passive"))
      (node (ref "TC15") (pin "4") (pinfunction "VIN-_4") (pintype "passive"))
    )
    (net (code "101") (name "Net-(TC16-ADDR)") (class "Default")
      (node (ref "R172") (pin "2") (pinfunction "2_2") (pintype "passive"))
      (node (ref "R176") (pin "1") (pinfunction "1_1") (pintype "passive"))
      (node (ref "TC16") (pin "16") (pinfunction "ADDR_16") (pintype "passive"))
    )
    (net (code "102") (name "Net-(TC16-ALERT1)") (class "Default")
      (node (ref "TC16") (pin "11") (pinfunction "ALERT1_11") (pintype "passive"))
      (node (ref "TP96") (pin "1") (pinfunction "1_1") (pintype "passive"))
    )
    (net (code "103") (name "Net-(TC16-ALERT2)") (class "Default")
      (node (ref "TC16") (pin "12") (pinfunction "ALERT2_12") (pintype "passive"))
      (node (ref "TP95") (pin "1") (pinfunction "1_1") (pintype "passive"))
    )
    (net (code "104") (name "Net-(TC16-ALERT3)") (class "Default")
      (node (ref "TC16") (pin "14") (pinfunction "ALERT3_14") (pintype "passive"))
      (node (ref "TP94") (pin "1") (pinfunction "1_1") (pintype "passive"))
    )
    (net (code "105") (name "Net-(TC16-ALERT4)") (class "Default")
      (node (ref "TC16") (pin "15") (pinfunction "ALERT4_15") (pintype "passive"))
      (node (ref "TP93") (pin "1") (pinfunction "1_1") (pintype "passive"))
    )
    (net (code "106") (name "Net-(TC16-OC_ALERT)") (class "Default")
      (node (ref "TC16") (pin "9") (pinfunction "OC_ALERT_9") (pintype "passive"))
      (node (ref "TP32") (pin "1") (pinfunction "1_1") (pintype "passive"))
    )
    (net (code "107") (name "Net-(TC16-SC_ALERT)") (class "Default")
      (node (ref "TC16") (pin "7") (pinfunction "SC_ALERT_7") (pintype "passive"))
      (node (ref "TP31") (pin "1") (pinfunction "1_1") (pintype "passive"))
    )
    (net (code "108") (name "Net-(TC16-VIN+)") (class "Default")
      (node (ref "C73") (pin "1") (pinfunction "1_1") (pintype "passive"))
      (node (ref "R174") (pin "2") (pinfunction "2_2") (pintype "passive"))
      (node (ref "R178") (pin "1") (pinfunction "1_1") (pintype "passive"))
      (node (ref "R185") (pin "1") (pinfunction "1_1") (pintype "passive"))
      (node (ref "TC16") (pin "2") (pinfunction "VIN+_2") (pintype "passive"))
      (node (ref "TC16") (pin "6") (pinfunction "V_SENSE_6") (pintype "passive"))
    )
    (net (code "109") (name "Net-(TC16-VIN-)") (class "Default")
      (node (ref "C73") (pin "2") (pinfunction "2_2") (pintype "passive"))
      (node (ref "R170") (pin "2") (pinfunction "2_2") (pintype "passive"))
      (node (ref "R186") (pin "1") (pinfunction "1_1") (pintype "passive"))
      (node (ref "TC16") (pin "4") (pinfunction "VIN-_4") (pintype "passive"))
    )
    (net (code "110") (name "PICO_ADA_3V3") (class "Default")
      (node (ref "C58") (pin "1") (pinfunction "1_1") (pintype "passive"))
      (node (ref "C59") (pin "1") (pinfunction "1_1") (pintype "passive"))
      (node (ref "C60") (pin "1") (pinfunction "1_1") (pintype "passive"))
      (node (ref "C64") (pin "1") (pinfunction "1_1") (pintype "passive"))
      (node (ref "C65") (pin "1") (pinfunction "1_1") (pintype "passive"))
      (node (ref "C66") (pin "1") (pinfunction "1_1") (pintype "passive"))
      (node (ref "C70") (pin "1") (pinfunction "1_1") (pintype "passive"))
      (node (ref "C71") (pin "1") (pinfunction "1_1") (pintype "passive"))
      (node (ref "R124") (pin "2") (pinfunction "2_2") (pintype "passive"))
      (node (ref "R125") (pin "2") (pinfunction "2_2") (pintype "passive"))
      (node (ref "R126") (pin "2") (pinfunction "2_2") (pintype "passive"))
      (node (ref "R127") (pin "2") (pinfunction "2_2") (pintype "passive"))
      (node (ref "R128") (pin "2") (pinfunction "2_2") (pintype "passive"))
      (node (ref "R129") (pin "2") (pinfunction "2_2") (pintype "passive"))
      (node (ref "R130") (pin "2") (pinfunction "2_2") (pintype "passive"))
      (node (ref "R131") (pin "2") (pinfunction "2_2") (pintype "passive"))
      (node (ref "R132") (pin "2") (pinfunction "2_2") (pintype "passive"))
      (node (ref "R133") (pin "2") (pinfunction "2_2") (pintype "passive"))
      (node (ref "R134") (pin "2") (pinfunction "2_2") (pintype "passive"))
      (node (ref "R135") (pin "2") (pinfunction "2_2") (pintype "passive"))
      (node (ref "R151") (pin "2") (pinfunction "2_2") (pintype "passive"))
      (node (ref "R152") (pin "2") (pinfunction "2_2") (pintype "passive"))
      (node (ref "R153") (pin "2") (pinfunction "2_2") (pintype "passive"))
      (node (ref "R154") (pin "2") (pinfunction "2_2") (pintype "passive"))
      (node (ref "R155") (pin "2") (pinfunction "2_2") (pintype "passive"))
      (node (ref "R156") (pin "2") (pinfunction "2_2") (pintype "passive"))
      (node (ref "R157") (pin "2") (pinfunction "2_2") (pintype "passive"))
      (node (ref "R158") (pin "2") (pinfunction "2_2") (pintype "passive"))
      (node (ref "R159") (pin "2") (pinfunction "2_2") (pintype "passive"))
      (node (ref "R160") (pin "2") (pinfunction "2_2") (pintype "passive"))
      (node (ref "R161") (pin "2") (pinfunction "2_2") (pintype "passive"))
      (node (ref "R166") (pin "2") (pinfunction "2_2") (pintype "passive"))
      (node (ref "R175") (pin "2") (pinfunction "2_2") (pintype "passive"))
      (node (ref "R176") (pin "2") (pinfunction "2_2") (pintype "passive"))
      (node (ref "R177") (pin "2") (pinfunction "2_2") (pintype "passive"))
      (node (ref "R178") (pin "2") (pinfunction "2_2") (pintype "passive"))
      (node (ref "R179") (pin "2") (pinfunction "2_2") (pintype "passive"))
      (node (ref "R180") (pin "2") (pinfunction "2_2") (pintype "passive"))
      (node (ref "R181") (pin "2") (pinfunction "2_2") (pintype "passive"))
      (node (ref "R182") (pin "2") (pinfunction "2_2") (pintype "passive"))
      (node (ref "TC10") (pin "8") (pinfunction "VDD_8") (pintype "passive"))
      (node (ref "TC11") (pin "8") (pinfunction "VDD_8") (pintype "passive"))
      (node (ref "TC12") (pin "8") (pinfunction "VDD_8") (pintype "passive"))
      (node (ref "TC13") (pin "8") (pinfunction "VDD_8") (pintype "passive"))
      (node (ref "TC14") (pin "8") (pinfunction "VDD_8") (pintype "passive"))
      (node (ref "TC15") (pin "8") (pinfunction "VDD_8") (pintype "passive"))
      (node (ref "TC16") (pin "8") (pinfunction "VDD_8") (pintype "passive"))
      (node (ref "TC9") (pin "8") (pinfunction "VDD_8") (pintype "passive"))
    )
  )
)
